# RX08.net
KiCad netlist of a schematic drawn in EAGLE
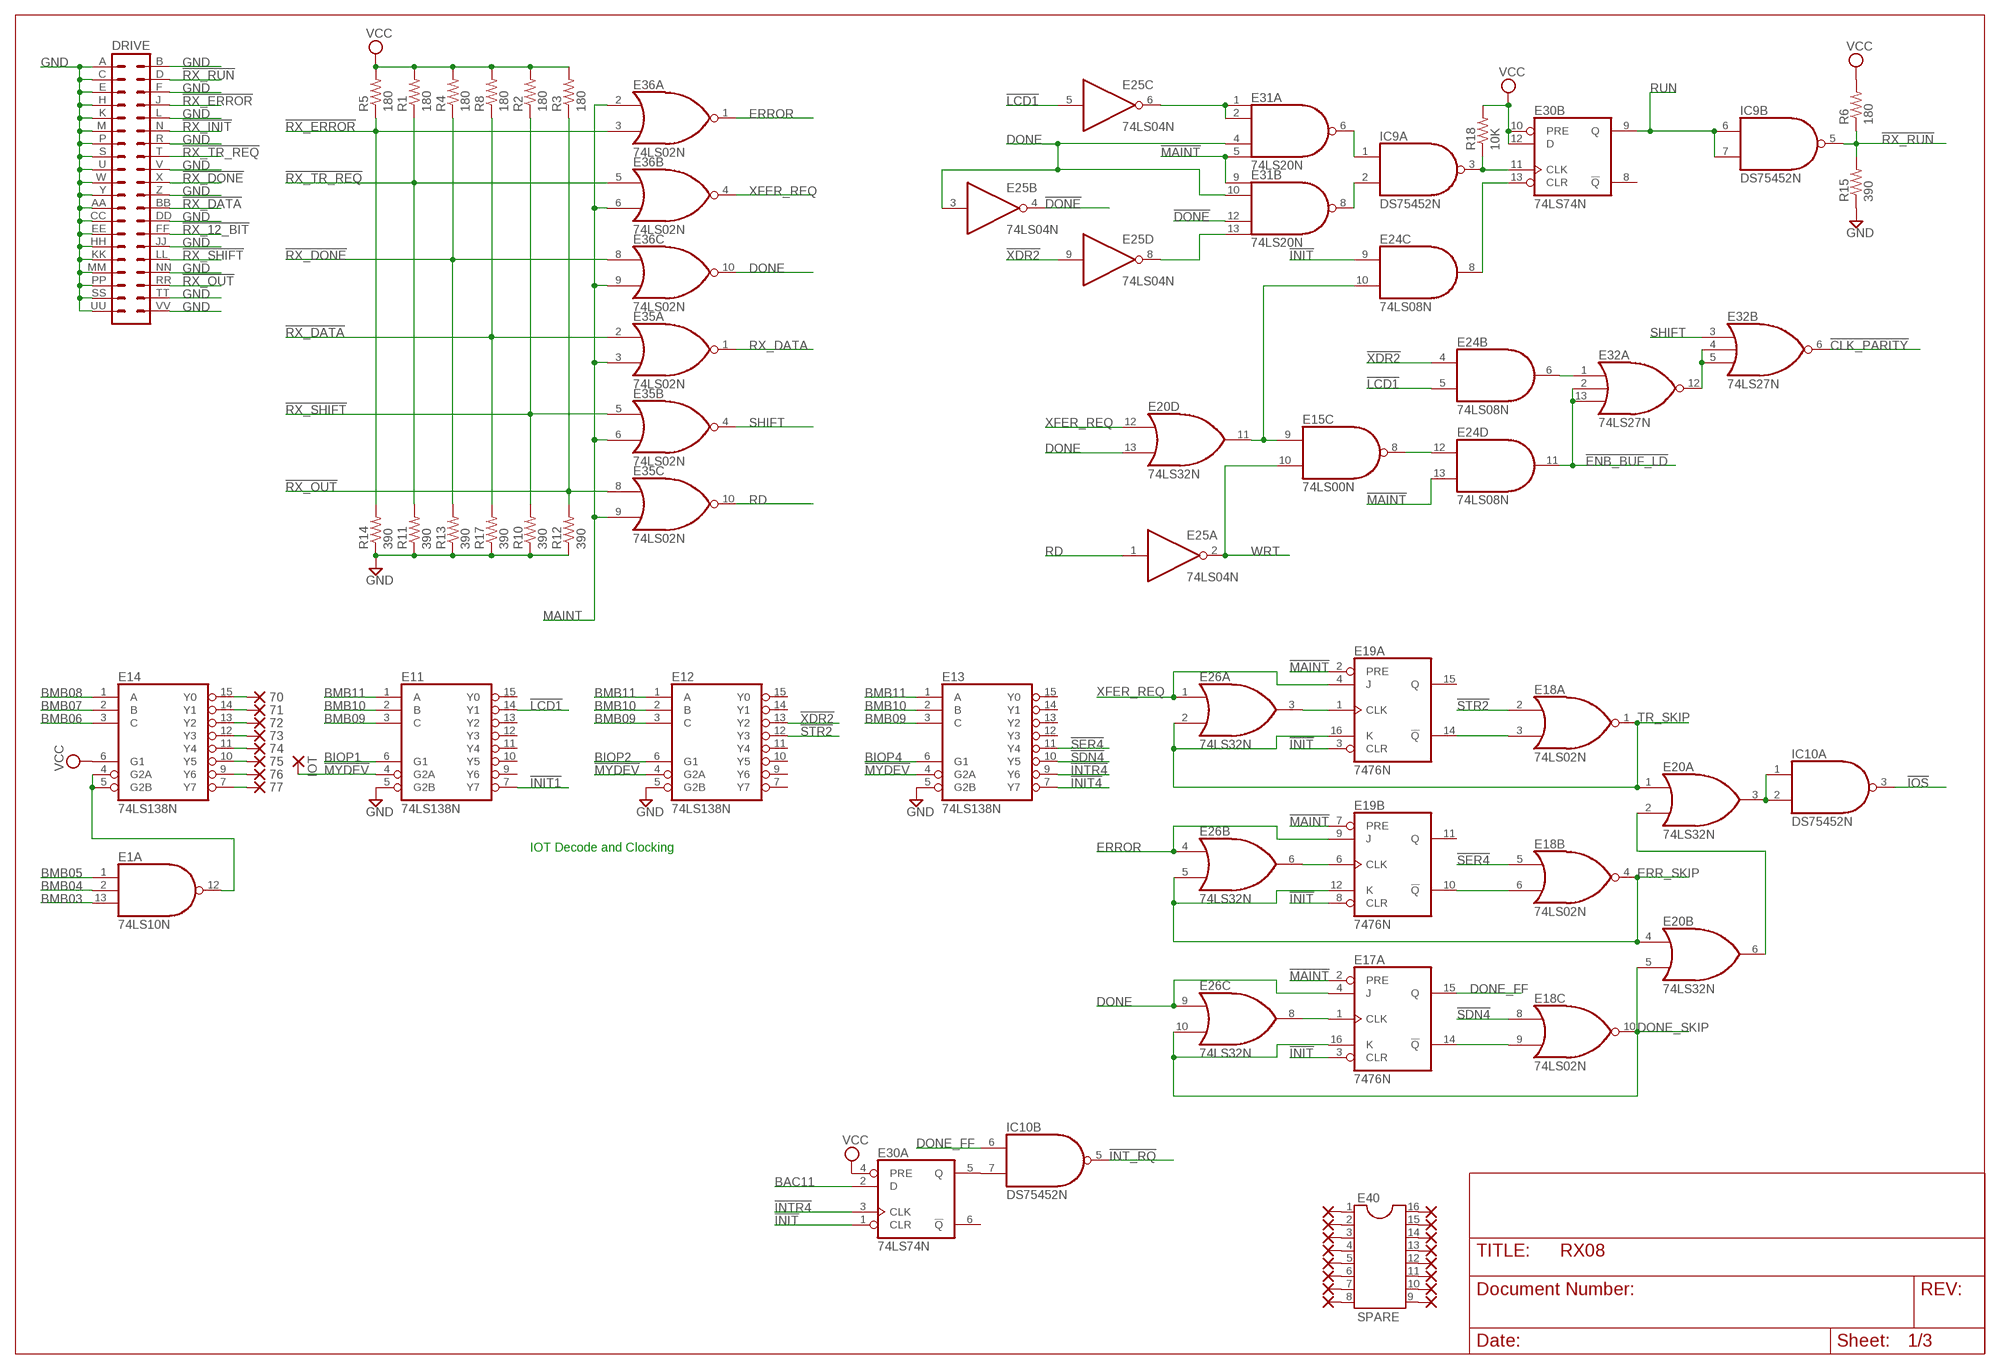
[diagram p0: schematic, sheet 1]
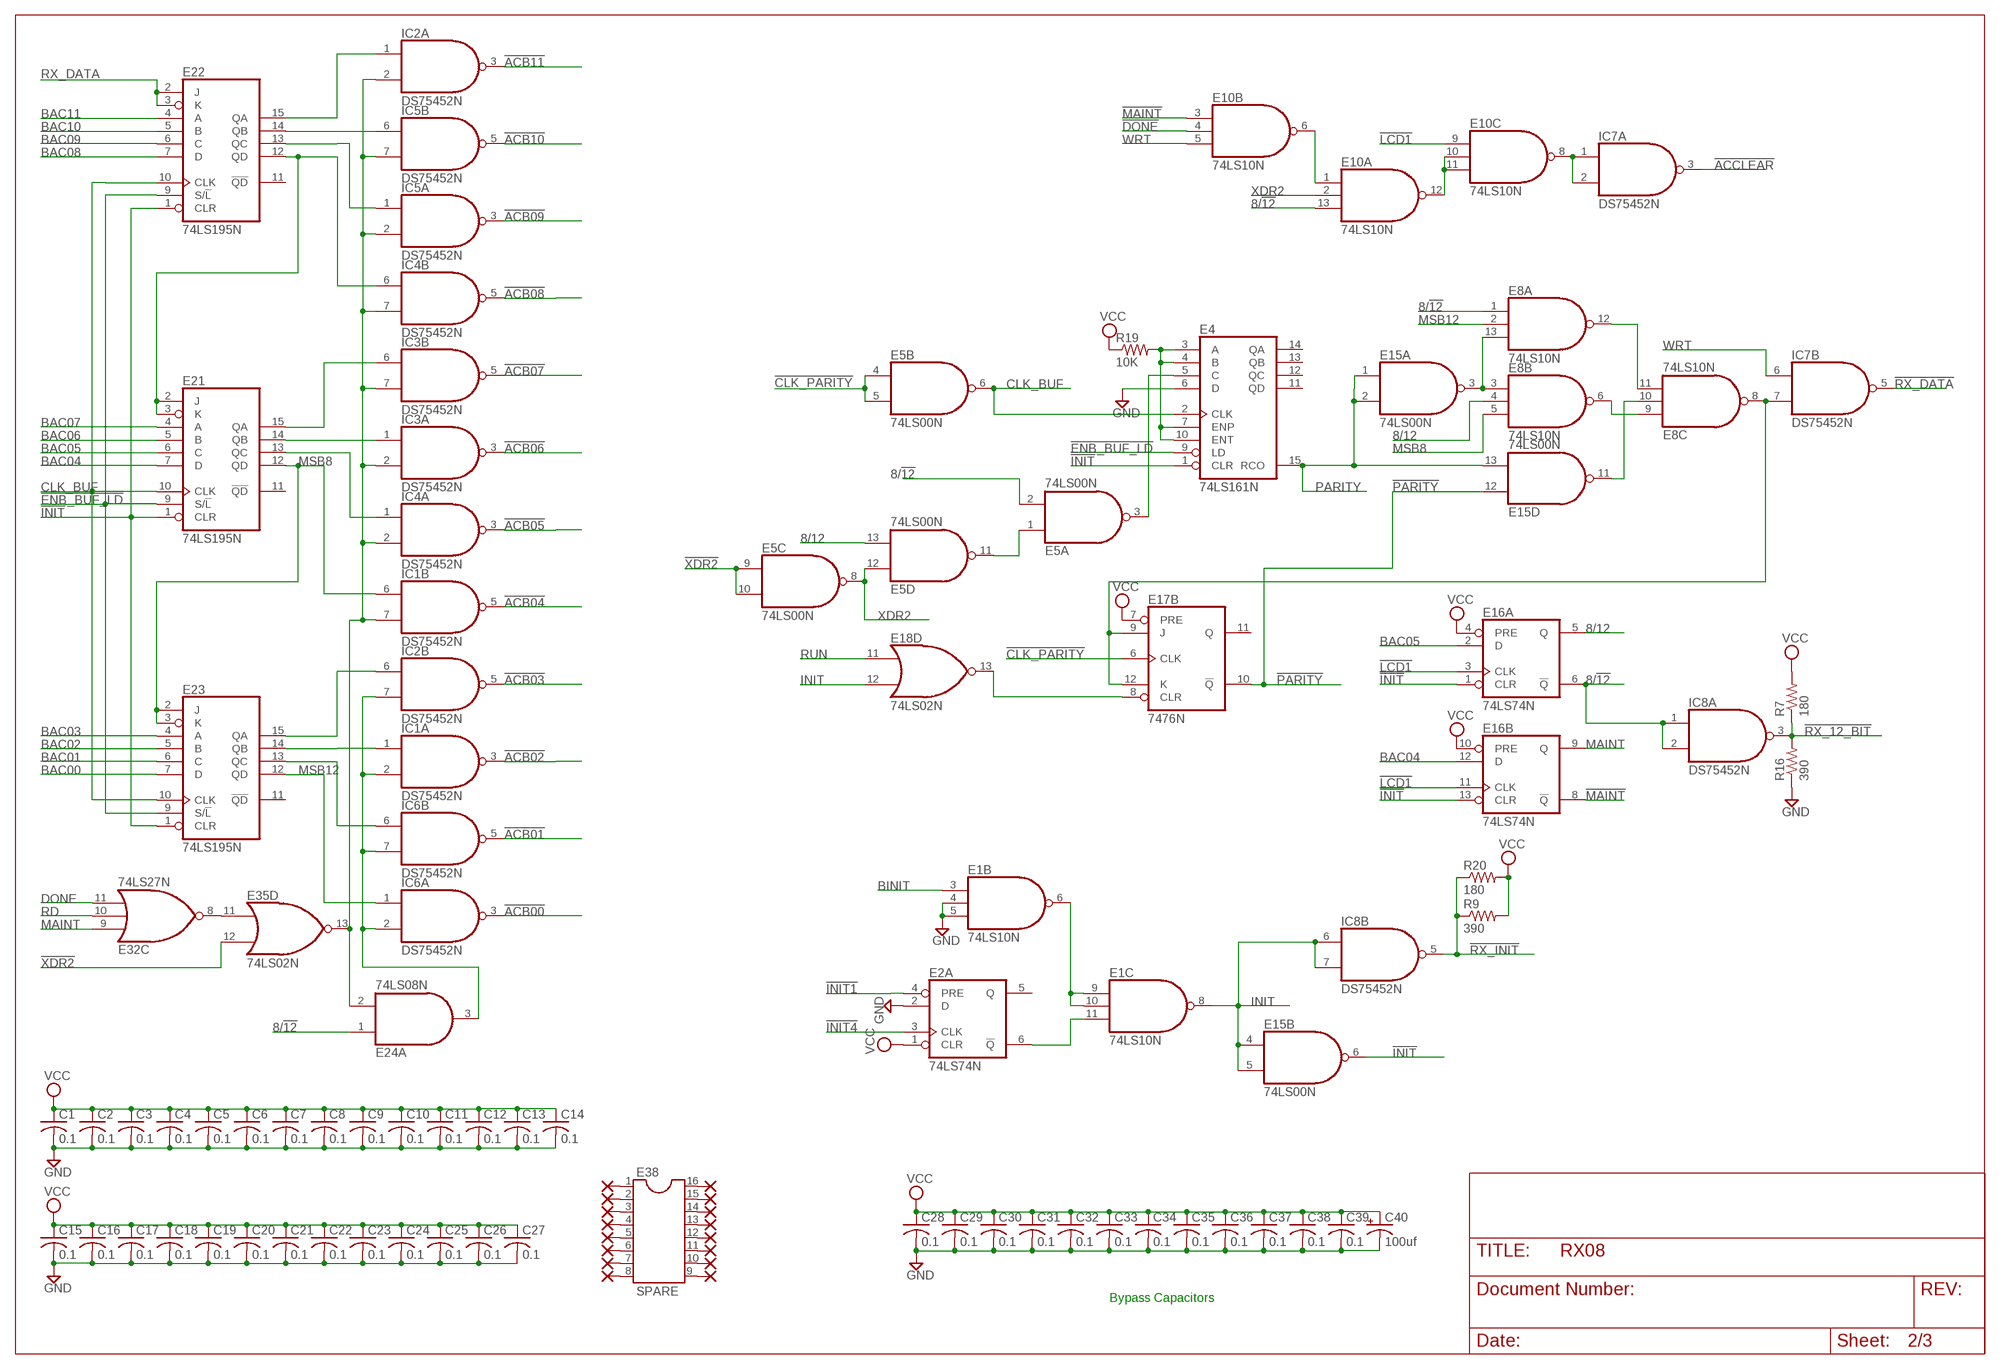
[diagram p1: schematic, sheet 2]
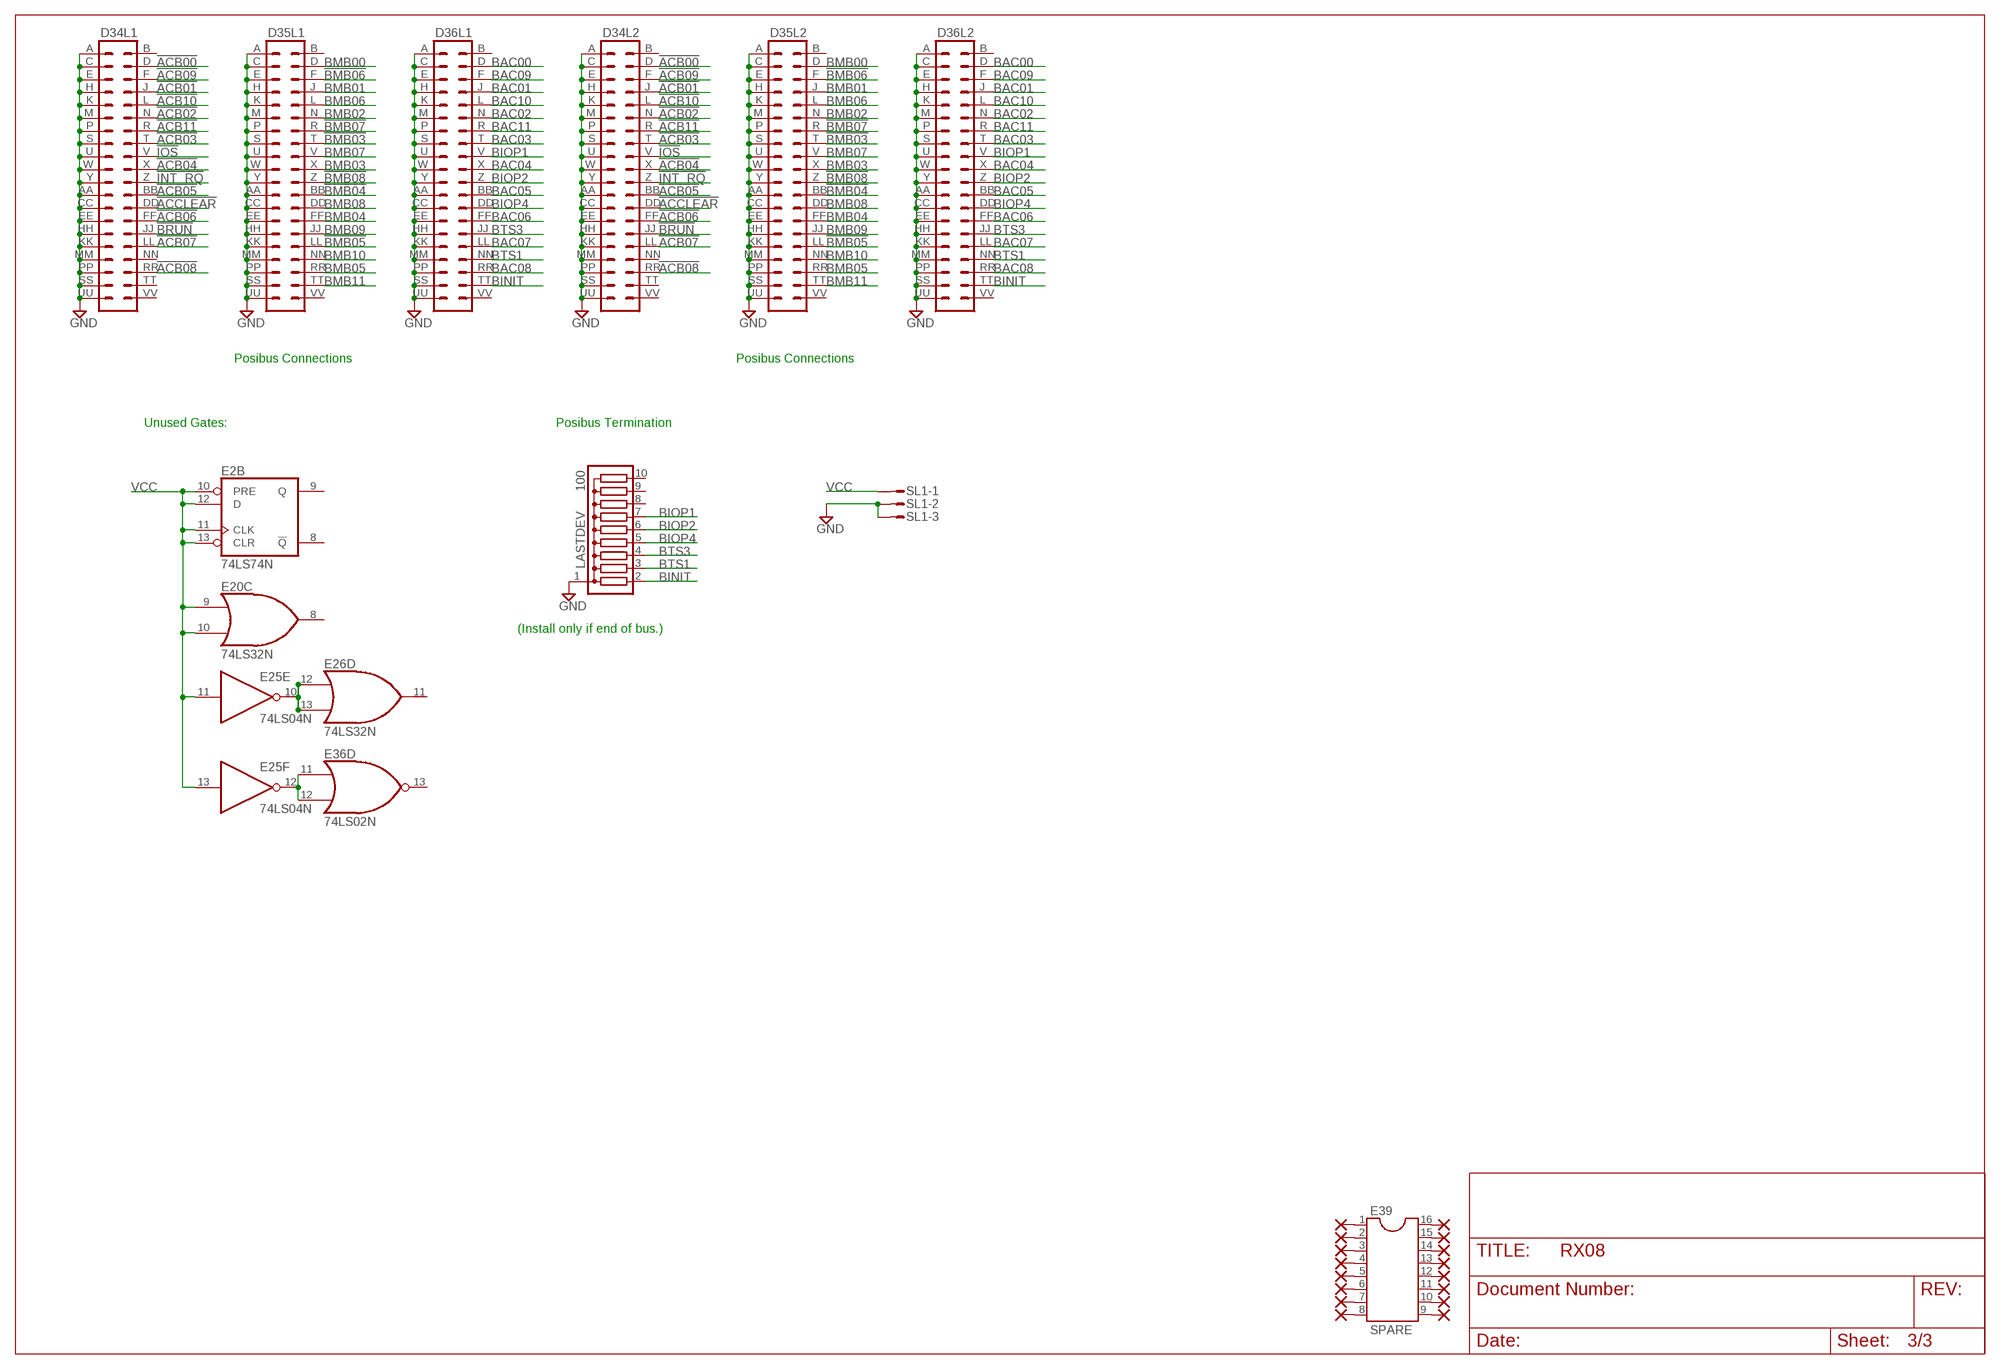
[diagram p2: schematic, sheet 3]

(export (version "E")
  (design (tool "Eeschema 10.0.6"))
  (components
    (comp (ref "C1")
      (value "0.1")
      (footprint "eagle-import:C050-025X075")
      (libsource (lib "eagle-import") (part "C-US050-025X075"))
    )
    (comp (ref "C2")
      (value "0.1")
      (footprint "eagle-import:C050-025X075")
      (libsource (lib "eagle-import") (part "C-US050-025X075"))
    )
    (comp (ref "C3")
      (value "0.1")
      (footprint "eagle-import:C050-025X075")
      (libsource (lib "eagle-import") (part "C-US050-025X075"))
    )
    (comp (ref "C4")
      (value "0.1")
      (footprint "eagle-import:C050-025X075")
      (libsource (lib "eagle-import") (part "C-US050-025X075"))
    )
    (comp (ref "C5")
      (value "0.1")
      (footprint "eagle-import:C050-025X075")
      (libsource (lib "eagle-import") (part "C-US050-025X075"))
    )
    (comp (ref "C6")
      (value "0.1")
      (footprint "eagle-import:C050-025X075")
      (libsource (lib "eagle-import") (part "C-US050-025X075"))
    )
    (comp (ref "C7")
      (value "0.1")
      (footprint "eagle-import:C050-025X075")
      (libsource (lib "eagle-import") (part "C-US050-025X075"))
    )
    (comp (ref "C8")
      (value "0.1")
      (footprint "eagle-import:C050-025X075")
      (libsource (lib "eagle-import") (part "C-US050-025X075"))
    )
    (comp (ref "C9")
      (value "0.1")
      (footprint "eagle-import:C050-025X075")
      (libsource (lib "eagle-import") (part "C-US050-025X075"))
    )
    (comp (ref "C10")
      (value "0.1")
      (footprint "eagle-import:C050-025X075")
      (libsource (lib "eagle-import") (part "C-US050-025X075"))
    )
    (comp (ref "C11")
      (value "0.1")
      (footprint "eagle-import:C050-025X075")
      (libsource (lib "eagle-import") (part "C-US050-025X075"))
    )
    (comp (ref "C12")
      (value "0.1")
      (footprint "eagle-import:C050-025X075")
      (libsource (lib "eagle-import") (part "C-US050-025X075"))
    )
    (comp (ref "C13")
      (value "0.1")
      (footprint "eagle-import:C050-025X075")
      (libsource (lib "eagle-import") (part "C-US050-025X075"))
    )
    (comp (ref "C14")
      (value "0.1")
      (footprint "eagle-import:C050-025X075")
      (libsource (lib "eagle-import") (part "C-US050-025X075"))
    )
    (comp (ref "C15")
      (value "0.1")
      (footprint "eagle-import:C050-025X075")
      (libsource (lib "eagle-import") (part "C-US050-025X075"))
    )
    (comp (ref "C16")
      (value "0.1")
      (footprint "eagle-import:C050-025X075")
      (libsource (lib "eagle-import") (part "C-US050-025X075"))
    )
    (comp (ref "C17")
      (value "0.1")
      (footprint "eagle-import:C050-025X075")
      (libsource (lib "eagle-import") (part "C-US050-025X075"))
    )
    (comp (ref "C18")
      (value "0.1")
      (footprint "eagle-import:C050-025X075")
      (libsource (lib "eagle-import") (part "C-US050-025X075"))
    )
    (comp (ref "C19")
      (value "0.1")
      (footprint "eagle-import:C050-025X075")
      (libsource (lib "eagle-import") (part "C-US050-025X075"))
    )
    (comp (ref "C20")
      (value "0.1")
      (footprint "eagle-import:C050-025X075")
      (libsource (lib "eagle-import") (part "C-US050-025X075"))
    )
    (comp (ref "C21")
      (value "0.1")
      (footprint "eagle-import:C050-025X075")
      (libsource (lib "eagle-import") (part "C-US050-025X075"))
    )
    (comp (ref "C22")
      (value "0.1")
      (footprint "eagle-import:C050-025X075")
      (libsource (lib "eagle-import") (part "C-US050-025X075"))
    )
    (comp (ref "C23")
      (value "0.1")
      (footprint "eagle-import:C050-025X075")
      (libsource (lib "eagle-import") (part "C-US050-025X075"))
    )
    (comp (ref "C24")
      (value "0.1")
      (footprint "eagle-import:C050-025X075")
      (libsource (lib "eagle-import") (part "C-US050-025X075"))
    )
    (comp (ref "C25")
      (value "0.1")
      (footprint "eagle-import:C050-025X075")
      (libsource (lib "eagle-import") (part "C-US050-025X075"))
    )
    (comp (ref "C26")
      (value "0.1")
      (footprint "eagle-import:C050-025X075")
      (libsource (lib "eagle-import") (part "C-US050-025X075"))
    )
    (comp (ref "C27")
      (value "0.1")
      (footprint "eagle-import:C050-025X075")
      (libsource (lib "eagle-import") (part "C-US050-025X075"))
    )
    (comp (ref "C28")
      (value "0.1")
      (footprint "eagle-import:C050-025X075")
      (libsource (lib "eagle-import") (part "C-US050-025X075"))
    )
    (comp (ref "C29")
      (value "0.1")
      (footprint "eagle-import:C050-025X075")
      (libsource (lib "eagle-import") (part "C-US050-025X075"))
    )
    (comp (ref "C30")
      (value "0.1")
      (footprint "eagle-import:C050-025X075")
      (libsource (lib "eagle-import") (part "C-US050-025X075"))
    )
    (comp (ref "C31")
      (value "0.1")
      (footprint "eagle-import:C050-025X075")
      (libsource (lib "eagle-import") (part "C-US050-025X075"))
    )
    (comp (ref "C32")
      (value "0.1")
      (footprint "eagle-import:C050-025X075")
      (libsource (lib "eagle-import") (part "C-US050-025X075"))
    )
    (comp (ref "C33")
      (value "0.1")
      (footprint "eagle-import:C050-025X075")
      (libsource (lib "eagle-import") (part "C-US050-025X075"))
    )
    (comp (ref "C34")
      (value "0.1")
      (footprint "eagle-import:C050-025X075")
      (libsource (lib "eagle-import") (part "C-US050-025X075"))
    )
    (comp (ref "C35")
      (value "0.1")
      (footprint "eagle-import:C050-025X075")
      (libsource (lib "eagle-import") (part "C-US050-025X075"))
    )
    (comp (ref "C36")
      (value "0.1")
      (footprint "eagle-import:C050-025X075")
      (libsource (lib "eagle-import") (part "C-US050-025X075"))
    )
    (comp (ref "C37")
      (value "0.1")
      (footprint "eagle-import:C050-025X075")
      (libsource (lib "eagle-import") (part "C-US050-025X075"))
    )
    (comp (ref "C38")
      (value "0.1")
      (footprint "eagle-import:C050-025X075")
      (libsource (lib "eagle-import") (part "C-US050-025X075"))
    )
    (comp (ref "C39")
      (value "0.1")
      (footprint "eagle-import:C050-025X075")
      (libsource (lib "eagle-import") (part "C-US050-025X075"))
    )
    (comp (ref "C40")
      (value "100uf")
      (footprint "eagle-import:E22-9")
      (libsource (lib "eagle-import") (part "CPOL-USE22-9AXIAL"))
    )
    (comp (ref "E1")
      (value "74LS10N")
      (footprint "eagle-import:DIL14")
      (libsource (lib "eagle-import") (part "7410NLS"))
    )
    (comp (ref "E2")
      (value "74LS74N")
      (footprint "eagle-import:DIL14")
      (libsource (lib "eagle-import") (part "7474NLS"))
    )
    (comp (ref "E4")
      (value "74LS161N")
      (footprint "eagle-import:DIL16")
      (libsource (lib "eagle-import") (part "74161NLS"))
    )
    (comp (ref "E5")
      (value "74LS00N")
      (footprint "eagle-import:DIL14")
      (libsource (lib "eagle-import") (part "7400NLS"))
    )
    (comp (ref "E8")
      (value "74LS10N")
      (footprint "eagle-import:DIL14")
      (libsource (lib "eagle-import") (part "7410NLS"))
    )
    (comp (ref "E10")
      (value "74LS10N")
      (footprint "eagle-import:DIL14")
      (libsource (lib "eagle-import") (part "7410NLS"))
    )
    (comp (ref "E15")
      (value "74LS00N")
      (footprint "eagle-import:DIL14")
      (libsource (lib "eagle-import") (part "7400NLS"))
    )
    (comp (ref "E16")
      (value "74LS74N")
      (footprint "eagle-import:DIL14")
      (libsource (lib "eagle-import") (part "7474NLS"))
    )
    (comp (ref "E17")
      (value "7476N")
      (footprint "eagle-import:DIL16")
      (libsource (lib "eagle-import") (part "7476N"))
    )
    (comp (ref "E18")
      (value "74LS02N")
      (footprint "eagle-import:DIL14")
      (libsource (lib "eagle-import") (part "7402NLS"))
    )
    (comp (ref "E21")
      (value "74LS195N")
      (footprint "eagle-import:DIL16")
      (libsource (lib "eagle-import") (part "74195NLS"))
    )
    (comp (ref "E22")
      (value "74LS195N")
      (footprint "eagle-import:DIL16")
      (libsource (lib "eagle-import") (part "74195NLS"))
    )
    (comp (ref "E23")
      (value "74LS195N")
      (footprint "eagle-import:DIL16")
      (libsource (lib "eagle-import") (part "74195NLS"))
    )
    (comp (ref "E24")
      (value "74LS08N")
      (footprint "eagle-import:DIL14")
      (libsource (lib "eagle-import") (part "7408NLS"))
    )
    (comp (ref "E32")
      (value "74LS27N")
      (footprint "eagle-import:DIL14")
      (libsource (lib "eagle-import") (part "7427NLS"))
    )
    (comp (ref "E35")
      (value "74LS02N")
      (footprint "eagle-import:DIL14")
      (libsource (lib "eagle-import") (part "7402NLS"))
    )
    (comp (ref "E38")
      (value "SPARE")
      (footprint "eagle-import:DIL16")
      (libsource (lib "eagle-import") (part "DIL16"))
    )
    (comp (ref "IC1")
      (value "DS75452N")
      (footprint "eagle-import:DIL08")
      (libsource (lib "eagle-import") (part "DS75452N"))
    )
    (comp (ref "IC2")
      (value "DS75452N")
      (footprint "eagle-import:DIL08")
      (libsource (lib "eagle-import") (part "DS75452N"))
    )
    (comp (ref "IC3")
      (value "DS75452N")
      (footprint "eagle-import:DIL08")
      (libsource (lib "eagle-import") (part "DS75452N"))
    )
    (comp (ref "IC4")
      (value "DS75452N")
      (footprint "eagle-import:DIL08")
      (libsource (lib "eagle-import") (part "DS75452N"))
    )
    (comp (ref "IC5")
      (value "DS75452N")
      (footprint "eagle-import:DIL08")
      (libsource (lib "eagle-import") (part "DS75452N"))
    )
    (comp (ref "IC6")
      (value "DS75452N")
      (footprint "eagle-import:DIL08")
      (libsource (lib "eagle-import") (part "DS75452N"))
    )
    (comp (ref "IC7")
      (value "DS75452N")
      (footprint "eagle-import:DIL08")
      (libsource (lib "eagle-import") (part "DS75452N"))
    )
    (comp (ref "IC8")
      (value "DS75452N")
      (footprint "eagle-import:DIL08")
      (libsource (lib "eagle-import") (part "DS75452N"))
    )
    (comp (ref "PAD10")
      (value "1,6/0,8")
      (footprint "eagle-import:1,6_0,8")
      (libsource (lib "eagle-import") (part "1,6/0,8"))
    )
    (comp (ref "PAD11")
      (value "1,6/0,8")
      (footprint "eagle-import:1,6_0,8")
      (libsource (lib "eagle-import") (part "1,6/0,8"))
    )
    (comp (ref "PAD12")
      (value "1,6/0,8")
      (footprint "eagle-import:1,6_0,8")
      (libsource (lib "eagle-import") (part "1,6/0,8"))
    )
    (comp (ref "PAD13")
      (value "1,6/0,8")
      (footprint "eagle-import:1,6_0,8")
      (libsource (lib "eagle-import") (part "1,6/0,8"))
    )
    (comp (ref "PAD14")
      (value "1,6/0,8")
      (footprint "eagle-import:1,6_0,8")
      (libsource (lib "eagle-import") (part "1,6/0,8"))
    )
    (comp (ref "PAD15")
      (value "1,6/0,8")
      (footprint "eagle-import:1,6_0,8")
      (libsource (lib "eagle-import") (part "1,6/0,8"))
    )
    (comp (ref "PAD16")
      (value "1,6/0,8")
      (footprint "eagle-import:1,6_0,8")
      (libsource (lib "eagle-import") (part "1,6/0,8"))
    )
    (comp (ref "PAD17")
      (value "1,6/0,8")
      (footprint "eagle-import:1,6_0,8")
      (libsource (lib "eagle-import") (part "1,6/0,8"))
    )
    (comp (ref "PAD20")
      (value "1,6/0,8")
      (footprint "eagle-import:1,6_0,8")
      (libsource (lib "eagle-import") (part "1,6/0,8"))
    )
    (comp (ref "PAD21")
      (value "1,6/0,8")
      (footprint "eagle-import:1,6_0,8")
      (libsource (lib "eagle-import") (part "1,6/0,8"))
    )
    (comp (ref "PAD22")
      (value "1,6/0,8")
      (footprint "eagle-import:1,6_0,8")
      (libsource (lib "eagle-import") (part "1,6/0,8"))
    )
    (comp (ref "PAD23")
      (value "1,6/0,8")
      (footprint "eagle-import:1,6_0,8")
      (libsource (lib "eagle-import") (part "1,6/0,8"))
    )
    (comp (ref "PAD24")
      (value "1,6/0,8")
      (footprint "eagle-import:1,6_0,8")
      (libsource (lib "eagle-import") (part "1,6/0,8"))
    )
    (comp (ref "PAD25")
      (value "1,6/0,8")
      (footprint "eagle-import:1,6_0,8")
      (libsource (lib "eagle-import") (part "1,6/0,8"))
    )
    (comp (ref "PAD26")
      (value "1,6/0,8")
      (footprint "eagle-import:1,6_0,8")
      (libsource (lib "eagle-import") (part "1,6/0,8"))
    )
    (comp (ref "PAD27")
      (value "1,6/0,8")
      (footprint "eagle-import:1,6_0,8")
      (libsource (lib "eagle-import") (part "1,6/0,8"))
    )
    (comp (ref "R7")
      (value "180")
      (footprint "eagle-import:0207_10")
      (libsource (lib "eagle-import") (part "R-US_0207/10"))
    )
    (comp (ref "R9")
      (value "390")
      (footprint "eagle-import:0207_10")
      (libsource (lib "eagle-import") (part "R-US_0207/10"))
    )
    (comp (ref "R16")
      (value "390")
      (footprint "eagle-import:0207_10")
      (libsource (lib "eagle-import") (part "R-US_0207/10"))
    )
    (comp (ref "R19")
      (value "10K")
      (footprint "eagle-import:0207_10")
      (libsource (lib "eagle-import") (part "R-US_0207/10"))
    )
    (comp (ref "R20")
      (value "180")
      (footprint "eagle-import:0207_10")
      (libsource (lib "eagle-import") (part "R-US_0207/10"))
    )
    (comp (ref "D34L1")
      (value "DEC40PINV")
      (footprint "eagle-import:DEC40PINV")
      (libsource (lib "eagle-import") (part "DEC40PINV"))
    )
    (comp (ref "D34L2")
      (value "DEC40PINV")
      (footprint "eagle-import:DEC40PINV")
      (libsource (lib "eagle-import") (part "DEC40PINV"))
    )
    (comp (ref "D35L1")
      (value "DEC40PINV")
      (footprint "eagle-import:DEC40PINV")
      (libsource (lib "eagle-import") (part "DEC40PINV"))
    )
    (comp (ref "D35L2")
      (value "DEC40PINV")
      (footprint "eagle-import:DEC40PINV")
      (libsource (lib "eagle-import") (part "DEC40PINV"))
    )
    (comp (ref "D36L1")
      (value "DEC40PINV")
      (footprint "eagle-import:DEC40PINV")
      (libsource (lib "eagle-import") (part "DEC40PINV"))
    )
    (comp (ref "D36L2")
      (value "DEC40PINV")
      (footprint "eagle-import:DEC40PINV")
      (libsource (lib "eagle-import") (part "DEC40PINV"))
    )
    (comp (ref "E20")
      (value "74LS32N")
      (footprint "eagle-import:DIL14")
      (libsource (lib "eagle-import") (part "7432NLS"))
    )
    (comp (ref "E25")
      (value "74LS04N")
      (footprint "eagle-import:DIL14")
      (libsource (lib "eagle-import") (part "7404NLS"))
    )
    (comp (ref "E26")
      (value "74LS32N")
      (footprint "eagle-import:DIL14")
      (libsource (lib "eagle-import") (part "7432NLS"))
    )
    (comp (ref "E36")
      (value "74LS02N")
      (footprint "eagle-import:DIL14")
      (libsource (lib "eagle-import") (part "7402NLS"))
    )
    (comp (ref "E39")
      (value "SPARE")
      (footprint "eagle-import:DIL16")
      (libsource (lib "eagle-import") (part "DIL16"))
    )
    (comp (ref "LASTDEV")
      (value "100")
      (footprint "eagle-import:SIL10")
      (libsource (lib "eagle-import") (part "G09R"))
    )
    (comp (ref "PAD42")
      (value "1,6/0,8")
      (footprint "eagle-import:1,6_0,8")
      (libsource (lib "eagle-import") (part "1,6/0,8"))
    )
    (comp (ref "PAD43")
      (value "1,6/0,8")
      (footprint "eagle-import:1,6_0,8")
      (libsource (lib "eagle-import") (part "1,6/0,8"))
    )
    (comp (ref "PAD44")
      (value "1,6/0,8")
      (footprint "eagle-import:1,6_0,8")
      (libsource (lib "eagle-import") (part "1,6/0,8"))
    )
    (comp (ref "PAD45")
      (value "1,6/0,8")
      (footprint "eagle-import:1,6_0,8")
      (libsource (lib "eagle-import") (part "1,6/0,8"))
    )
    (comp (ref "PAD46")
      (value "1,6/0,8")
      (footprint "eagle-import:1,6_0,8")
      (libsource (lib "eagle-import") (part "1,6/0,8"))
    )
    (comp (ref "PAD47")
      (value "1,6/0,8")
      (footprint "eagle-import:1,6_0,8")
      (libsource (lib "eagle-import") (part "1,6/0,8"))
    )
    (comp (ref "PAD48")
      (value "1,6/0,8")
      (footprint "eagle-import:1,6_0,8")
      (libsource (lib "eagle-import") (part "1,6/0,8"))
    )
    (comp (ref "PAD49")
      (value "1,6/0,8")
      (footprint "eagle-import:1,6_0,8")
      (libsource (lib "eagle-import") (part "1,6/0,8"))
    )
    (comp (ref "PAD50")
      (value "1,6/0,8")
      (footprint "eagle-import:1,6_0,8")
      (libsource (lib "eagle-import") (part "1,6/0,8"))
    )
    (comp (ref "PAD51")
      (value "1,6/0,8")
      (footprint "eagle-import:1,6_0,8")
      (libsource (lib "eagle-import") (part "1,6/0,8"))
    )
    (comp (ref "PAD52")
      (value "1,6/0,8")
      (footprint "eagle-import:1,6_0,8")
      (libsource (lib "eagle-import") (part "1,6/0,8"))
    )
    (comp (ref "PAD53")
      (value "1,6/0,8")
      (footprint "eagle-import:1,6_0,8")
      (libsource (lib "eagle-import") (part "1,6/0,8"))
    )
    (comp (ref "PAD54")
      (value "1,6/0,8")
      (footprint "eagle-import:1,6_0,8")
      (libsource (lib "eagle-import") (part "1,6/0,8"))
    )
    (comp (ref "PAD55")
      (value "1,6/0,8")
      (footprint "eagle-import:1,6_0,8")
      (libsource (lib "eagle-import") (part "1,6/0,8"))
    )
    (comp (ref "PAD56")
      (value "1,6/0,8")
      (footprint "eagle-import:1,6_0,8")
      (libsource (lib "eagle-import") (part "1,6/0,8"))
    )
    (comp (ref "PAD57")
      (value "1,6/0,8")
      (footprint "eagle-import:1,6_0,8")
      (libsource (lib "eagle-import") (part "1,6/0,8"))
    )
    (comp (ref "SL1")
      (value "MA04S")
      (footprint "eagle-import:04PA")
      (libsource (lib "eagle-import") (part "MA04S"))
    )
    (comp (ref "70")
      (value "1,6/0,8")
      (footprint "eagle-import:1,6_0,8")
      (libsource (lib "eagle-import") (part "1,6/0,8"))
    )
    (comp (ref "71")
      (value "1,6/0,8")
      (footprint "eagle-import:1,6_0,8")
      (libsource (lib "eagle-import") (part "1,6/0,8"))
    )
    (comp (ref "72")
      (value "1,6/0,8")
      (footprint "eagle-import:1,6_0,8")
      (libsource (lib "eagle-import") (part "1,6/0,8"))
    )
    (comp (ref "73")
      (value "1,6/0,8")
      (footprint "eagle-import:1,6_0,8")
      (libsource (lib "eagle-import") (part "1,6/0,8"))
    )
    (comp (ref "74")
      (value "1,6/0,8")
      (footprint "eagle-import:1,6_0,8")
      (libsource (lib "eagle-import") (part "1,6/0,8"))
    )
    (comp (ref "75")
      (value "1,6/0,8")
      (footprint "eagle-import:1,6_0,8")
      (libsource (lib "eagle-import") (part "1,6/0,8"))
    )
    (comp (ref "76")
      (value "1,6/0,8")
      (footprint "eagle-import:1,6_0,8")
      (libsource (lib "eagle-import") (part "1,6/0,8"))
    )
    (comp (ref "77")
      (value "1,6/0,8")
      (footprint "eagle-import:1,6_0,8")
      (libsource (lib "eagle-import") (part "1,6/0,8"))
    )
    (comp (ref "DRIVE")
      (value "DEC40PINV")
      (footprint "eagle-import:DEC40PINV")
      (libsource (lib "eagle-import") (part "DEC40PINV"))
    )
    (comp (ref "E11")
      (value "74LS138N")
      (footprint "eagle-import:DIL16")
      (libsource (lib "eagle-import") (part "74138NLS"))
    )
    (comp (ref "E12")
      (value "74LS138N")
      (footprint "eagle-import:DIL16")
      (libsource (lib "eagle-import") (part "74138NLS"))
    )
    (comp (ref "E13")
      (value "74LS138N")
      (footprint "eagle-import:DIL16")
      (libsource (lib "eagle-import") (part "74138NLS"))
    )
    (comp (ref "E14")
      (value "74LS138N")
      (footprint "eagle-import:DIL16")
      (libsource (lib "eagle-import") (part "74138NLS"))
    )
    (comp (ref "E19")
      (value "7476N")
      (footprint "eagle-import:DIL16")
      (libsource (lib "eagle-import") (part "7476N"))
    )
    (comp (ref "E30")
      (value "74LS74N")
      (footprint "eagle-import:DIL14")
      (libsource (lib "eagle-import") (part "7474NLS"))
    )
    (comp (ref "E31")
      (value "74LS20N")
      (footprint "eagle-import:DIL14")
      (libsource (lib "eagle-import") (part "7420NLS"))
    )
    (comp (ref "E40")
      (value "SPARE")
      (footprint "eagle-import:DIL16")
      (libsource (lib "eagle-import") (part "DIL16"))
    )
    (comp (ref "IC9")
      (value "DS75452N")
      (footprint "eagle-import:DIL08")
      (libsource (lib "eagle-import") (part "DS75452N"))
    )
    (comp (ref "IC10")
      (value "DS75452N")
      (footprint "eagle-import:DIL08")
      (libsource (lib "eagle-import") (part "DS75452N"))
    )
    (comp (ref "IOT")
      (value "1,6/0,8")
      (footprint "eagle-import:1,6_0,8")
      (libsource (lib "eagle-import") (part "1,6/0,8"))
    )
    (comp (ref "PAD18")
      (value "1,6/0,8")
      (footprint "eagle-import:1,6_0,8")
      (libsource (lib "eagle-import") (part "1,6/0,8"))
    )
    (comp (ref "PAD19")
      (value "1,6/0,8")
      (footprint "eagle-import:1,6_0,8")
      (libsource (lib "eagle-import") (part "1,6/0,8"))
    )
    (comp (ref "PAD28")
      (value "1,6/0,8")
      (footprint "eagle-import:1,6_0,8")
      (libsource (lib "eagle-import") (part "1,6/0,8"))
    )
    (comp (ref "PAD29")
      (value "1,6/0,8")
      (footprint "eagle-import:1,6_0,8")
      (libsource (lib "eagle-import") (part "1,6/0,8"))
    )
    (comp (ref "PAD30")
      (value "1,6/0,8")
      (footprint "eagle-import:1,6_0,8")
      (libsource (lib "eagle-import") (part "1,6/0,8"))
    )
    (comp (ref "PAD31")
      (value "1,6/0,8")
      (footprint "eagle-import:1,6_0,8")
      (libsource (lib "eagle-import") (part "1,6/0,8"))
    )
    (comp (ref "PAD32")
      (value "1,6/0,8")
      (footprint "eagle-import:1,6_0,8")
      (libsource (lib "eagle-import") (part "1,6/0,8"))
    )
    (comp (ref "PAD33")
      (value "1,6/0,8")
      (footprint "eagle-import:1,6_0,8")
      (libsource (lib "eagle-import") (part "1,6/0,8"))
    )
    (comp (ref "PAD34")
      (value "1,6/0,8")
      (footprint "eagle-import:1,6_0,8")
      (libsource (lib "eagle-import") (part "1,6/0,8"))
    )
    (comp (ref "PAD35")
      (value "1,6/0,8")
      (footprint "eagle-import:1,6_0,8")
      (libsource (lib "eagle-import") (part "1,6/0,8"))
    )
    (comp (ref "PAD36")
      (value "1,6/0,8")
      (footprint "eagle-import:1,6_0,8")
      (libsource (lib "eagle-import") (part "1,6/0,8"))
    )
    (comp (ref "PAD37")
      (value "1,6/0,8")
      (footprint "eagle-import:1,6_0,8")
      (libsource (lib "eagle-import") (part "1,6/0,8"))
    )
    (comp (ref "PAD38")
      (value "1,6/0,8")
      (footprint "eagle-import:1,6_0,8")
      (libsource (lib "eagle-import") (part "1,6/0,8"))
    )
    (comp (ref "PAD39")
      (value "1,6/0,8")
      (footprint "eagle-import:1,6_0,8")
      (libsource (lib "eagle-import") (part "1,6/0,8"))
    )
    (comp (ref "PAD40")
      (value "1,6/0,8")
      (footprint "eagle-import:1,6_0,8")
      (libsource (lib "eagle-import") (part "1,6/0,8"))
    )
    (comp (ref "PAD41")
      (value "1,6/0,8")
      (footprint "eagle-import:1,6_0,8")
      (libsource (lib "eagle-import") (part "1,6/0,8"))
    )
    (comp (ref "R1")
      (value "180")
      (footprint "eagle-import:0207_10")
      (libsource (lib "eagle-import") (part "R-US_0207/10"))
    )
    (comp (ref "R2")
      (value "180")
      (footprint "eagle-import:0207_10")
      (libsource (lib "eagle-import") (part "R-US_0207/10"))
    )
    (comp (ref "R3")
      (value "180")
      (footprint "eagle-import:0207_10")
      (libsource (lib "eagle-import") (part "R-US_0207/10"))
    )
    (comp (ref "R4")
      (value "180")
      (footprint "eagle-import:0207_10")
      (libsource (lib "eagle-import") (part "R-US_0207/10"))
    )
    (comp (ref "R5")
      (value "180")
      (footprint "eagle-import:0207_10")
      (libsource (lib "eagle-import") (part "R-US_0207/10"))
    )
    (comp (ref "R6")
      (value "180")
      (footprint "eagle-import:0207_10")
      (libsource (lib "eagle-import") (part "R-US_0207/10"))
    )
    (comp (ref "R8")
      (value "180")
      (footprint "eagle-import:0207_10")
      (libsource (lib "eagle-import") (part "R-US_0207/10"))
    )
    (comp (ref "R10")
      (value "390")
      (footprint "eagle-import:0207_10")
      (libsource (lib "eagle-import") (part "R-US_0207/10"))
    )
    (comp (ref "R11")
      (value "390")
      (footprint "eagle-import:0207_10")
      (libsource (lib "eagle-import") (part "R-US_0207/10"))
    )
    (comp (ref "R12")
      (value "390")
      (footprint "eagle-import:0207_10")
      (libsource (lib "eagle-import") (part "R-US_0207/10"))
    )
    (comp (ref "R13")
      (value "390")
      (footprint "eagle-import:0207_10")
      (libsource (lib "eagle-import") (part "R-US_0207/10"))
    )
    (comp (ref "R14")
      (value "390")
      (footprint "eagle-import:0207_10")
      (libsource (lib "eagle-import") (part "R-US_0207/10"))
    )
    (comp (ref "R15")
      (value "390")
      (footprint "eagle-import:0207_10")
      (libsource (lib "eagle-import") (part "R-US_0207/10"))
    )
    (comp (ref "R17")
      (value "390")
      (footprint "eagle-import:0207_10")
      (libsource (lib "eagle-import") (part "R-US_0207/10"))
    )
    (comp (ref "R18")
      (value "10K")
      (footprint "eagle-import:0207_10")
      (libsource (lib "eagle-import") (part "R-US_0207/10"))
    )
  )
  (nets
    (net (code "1") (name "8{slash}12") (class "Default")
      (node (ref "E16") (pin "5") (pinfunction "Q_5") (pintype "output"))
      (node (ref "E5") (pin "13") (pinfunction "I1_13") (pintype "input"))
      (node (ref "E8") (pin "4") (pinfunction "I1_4") (pintype "input"))
    )
    (net (code "2") (name "8{slash}~{12}") (class "Default")
      (node (ref "E10") (pin "13") (pinfunction "I2_13") (pintype "input"))
      (node (ref "E16") (pin "6") (pinfunction "~{Q}_6") (pintype "output"))
      (node (ref "E24") (pin "1") (pinfunction "I0_1") (pintype "input"))
      (node (ref "E5") (pin "2") (pinfunction "I1_2") (pintype "input"))
      (node (ref "E8") (pin "1") (pinfunction "I0_1") (pintype "input"))
      (node (ref "IC8") (pin "1") (pinfunction "I0_1") (pintype "input"))
      (node (ref "IC8") (pin "2") (pinfunction "I1_2") (pintype "input"))
    )
    (net (code "3") (name "BAC00") (class "Default")
      (node (ref "D36L1") (pin "D") (pinfunction "4_D") (pintype "bidirectional"))
      (node (ref "D36L2") (pin "D") (pinfunction "4_D") (pintype "bidirectional"))
      (node (ref "E23") (pin "7") (pinfunction "D_7") (pintype "input"))
    )
    (net (code "4") (name "BAC01") (class "Default")
      (node (ref "D36L1") (pin "J") (pinfunction "8_J") (pintype "bidirectional"))
      (node (ref "D36L2") (pin "J") (pinfunction "8_J") (pintype "bidirectional"))
      (node (ref "E23") (pin "6") (pinfunction "C_6") (pintype "input"))
    )
    (net (code "5") (name "BAC02") (class "Default")
      (node (ref "D36L1") (pin "N") (pinfunction "12_N") (pintype "bidirectional"))
      (node (ref "D36L2") (pin "N") (pinfunction "12_N") (pintype "bidirectional"))
      (node (ref "E23") (pin "5") (pinfunction "B_5") (pintype "input"))
    )
    (net (code "6") (name "BAC03") (class "Default")
      (node (ref "D36L1") (pin "T") (pinfunction "16_T") (pintype "bidirectional"))
      (node (ref "D36L2") (pin "T") (pinfunction "16_T") (pintype "bidirectional"))
      (node (ref "E23") (pin "4") (pinfunction "A_4") (pintype "input"))
    )
    (net (code "7") (name "BAC04") (class "Default")
      (node (ref "D36L1") (pin "X") (pinfunction "20_X") (pintype "bidirectional"))
      (node (ref "D36L2") (pin "X") (pinfunction "20_X") (pintype "bidirectional"))
      (node (ref "E16") (pin "12") (pinfunction "D_12") (pintype "input"))
      (node (ref "E21") (pin "7") (pinfunction "D_7") (pintype "input"))
    )
    (net (code "8") (name "BAC05") (class "Default")
      (node (ref "D36L1") (pin "BB") (pinfunction "24_BB") (pintype "bidirectional"))
      (node (ref "D36L2") (pin "BB") (pinfunction "24_BB") (pintype "bidirectional"))
      (node (ref "E16") (pin "2") (pinfunction "D_2") (pintype "input"))
      (node (ref "E21") (pin "6") (pinfunction "C_6") (pintype "input"))
    )
    (net (code "9") (name "BAC06") (class "Default")
      (node (ref "D36L1") (pin "FF") (pinfunction "28_FF") (pintype "bidirectional"))
      (node (ref "D36L2") (pin "FF") (pinfunction "28_FF") (pintype "bidirectional"))
      (node (ref "E21") (pin "5") (pinfunction "B_5") (pintype "input"))
    )
    (net (code "10") (name "BAC07") (class "Default")
      (node (ref "D36L1") (pin "LL") (pinfunction "32_LL") (pintype "bidirectional"))
      (node (ref "D36L2") (pin "LL") (pinfunction "32_LL") (pintype "bidirectional"))
      (node (ref "E21") (pin "4") (pinfunction "A_4") (pintype "input"))
    )
    (net (code "11") (name "BAC08") (class "Default")
      (node (ref "D36L1") (pin "RR") (pinfunction "36_RR") (pintype "bidirectional"))
      (node (ref "D36L2") (pin "RR") (pinfunction "36_RR") (pintype "bidirectional"))
      (node (ref "E22") (pin "7") (pinfunction "D_7") (pintype "input"))
    )
    (net (code "12") (name "BAC09") (class "Default")
      (node (ref "D36L1") (pin "F") (pinfunction "6_F") (pintype "bidirectional"))
      (node (ref "D36L2") (pin "F") (pinfunction "6_F") (pintype "bidirectional"))
      (node (ref "E22") (pin "6") (pinfunction "C_6") (pintype "input"))
    )
    (net (code "13") (name "BAC10") (class "Default")
      (node (ref "D36L1") (pin "L") (pinfunction "10_L") (pintype "bidirectional"))
      (node (ref "D36L2") (pin "L") (pinfunction "10_L") (pintype "bidirectional"))
      (node (ref "E22") (pin "5") (pinfunction "B_5") (pintype "input"))
    )
    (net (code "14") (name "BAC11") (class "Default")
      (node (ref "D36L1") (pin "R") (pinfunction "14_R") (pintype "bidirectional"))
      (node (ref "D36L2") (pin "R") (pinfunction "14_R") (pintype "bidirectional"))
      (node (ref "E22") (pin "4") (pinfunction "A_4") (pintype "input"))
      (node (ref "E30") (pin "2") (pinfunction "D_2") (pintype "input"))
    )
    (net (code "15") (name "BINIT") (class "Default")
      (node (ref "D36L1") (pin "TT") (pinfunction "38_TT") (pintype "bidirectional"))
      (node (ref "D36L2") (pin "TT") (pinfunction "38_TT") (pintype "bidirectional"))
      (node (ref "E1") (pin "3") (pinfunction "I0_3") (pintype "input"))
      (node (ref "LASTDEV") (pin "2") (pinfunction "2_2") (pintype "passive"))
    )
    (net (code "16") (name "BIOP1") (class "Default")
      (node (ref "D36L1") (pin "V") (pinfunction "18_V") (pintype "bidirectional"))
      (node (ref "D36L2") (pin "V") (pinfunction "18_V") (pintype "bidirectional"))
      (node (ref "E11") (pin "6") (pinfunction "G1_6") (pintype "input"))
      (node (ref "LASTDEV") (pin "7") (pinfunction "7_7") (pintype "passive"))
    )
    (net (code "17") (name "BIOP2") (class "Default")
      (node (ref "D36L1") (pin "Z") (pinfunction "22_Z") (pintype "bidirectional"))
      (node (ref "D36L2") (pin "Z") (pinfunction "22_Z") (pintype "bidirectional"))
      (node (ref "E12") (pin "6") (pinfunction "G1_6") (pintype "input"))
      (node (ref "LASTDEV") (pin "6") (pinfunction "6_6") (pintype "passive"))
    )
    (net (code "18") (name "BIOP4") (class "Default")
      (node (ref "D36L1") (pin "DD") (pinfunction "26_DD") (pintype "bidirectional"))
      (node (ref "D36L2") (pin "DD") (pinfunction "26_DD") (pintype "bidirectional"))
      (node (ref "E13") (pin "6") (pinfunction "G1_6") (pintype "input"))
      (node (ref "LASTDEV") (pin "5") (pinfunction "5_5") (pintype "passive"))
    )
    (net (code "19") (name "BMB00") (class "Default")
      (node (ref "D35L1") (pin "D") (pinfunction "4_D") (pintype "bidirectional"))
      (node (ref "D35L2") (pin "D") (pinfunction "4_D") (pintype "bidirectional"))
    )
    (net (code "20") (name "BMB01") (class "Default")
      (node (ref "D35L1") (pin "J") (pinfunction "8_J") (pintype "bidirectional"))
      (node (ref "D35L2") (pin "J") (pinfunction "8_J") (pintype "bidirectional"))
    )
    (net (code "21") (name "BMB02") (class "Default")
      (node (ref "D35L1") (pin "N") (pinfunction "12_N") (pintype "bidirectional"))
      (node (ref "D35L2") (pin "N") (pinfunction "12_N") (pintype "bidirectional"))
    )
    (net (code "22") (name "BMB03") (class "Default")
      (node (ref "D35L1") (pin "X") (pinfunction "20_X") (pintype "bidirectional"))
      (node (ref "D35L2") (pin "X") (pinfunction "20_X") (pintype "bidirectional"))
      (node (ref "E1") (pin "13") (pinfunction "I2_13") (pintype "input"))
    )
    (net (code "23") (name "BMB04") (class "Default")
      (node (ref "D35L1") (pin "FF") (pinfunction "28_FF") (pintype "bidirectional"))
      (node (ref "D35L2") (pin "FF") (pinfunction "28_FF") (pintype "bidirectional"))
      (node (ref "E1") (pin "2") (pinfunction "I1_2") (pintype "input"))
    )
    (net (code "24") (name "BMB05") (class "Default")
      (node (ref "D35L1") (pin "RR") (pinfunction "36_RR") (pintype "bidirectional"))
      (node (ref "D35L2") (pin "RR") (pinfunction "36_RR") (pintype "bidirectional"))
      (node (ref "E1") (pin "1") (pinfunction "I0_1") (pintype "input"))
    )
    (net (code "25") (name "BMB06") (class "Default")
      (node (ref "D35L1") (pin "L") (pinfunction "10_L") (pintype "bidirectional"))
      (node (ref "D35L2") (pin "L") (pinfunction "10_L") (pintype "bidirectional"))
      (node (ref "E14") (pin "3") (pinfunction "C_3") (pintype "input"))
    )
    (net (code "26") (name "BMB07") (class "Default")
      (node (ref "D35L1") (pin "V") (pinfunction "18_V") (pintype "bidirectional"))
      (node (ref "D35L2") (pin "V") (pinfunction "18_V") (pintype "bidirectional"))
      (node (ref "E14") (pin "2") (pinfunction "B_2") (pintype "input"))
    )
    (net (code "27") (name "BMB08") (class "Default")
      (node (ref "D35L1") (pin "DD") (pinfunction "26_DD") (pintype "bidirectional"))
      (node (ref "D35L2") (pin "DD") (pinfunction "26_DD") (pintype "bidirectional"))
      (node (ref "E14") (pin "1") (pinfunction "A_1") (pintype "input"))
    )
    (net (code "28") (name "BMB09") (class "Default")
      (node (ref "D35L1") (pin "JJ") (pinfunction "30_JJ") (pintype "bidirectional"))
      (node (ref "D35L2") (pin "JJ") (pinfunction "30_JJ") (pintype "bidirectional"))
      (node (ref "E11") (pin "3") (pinfunction "C_3") (pintype "input"))
      (node (ref "E12") (pin "3") (pinfunction "C_3") (pintype "input"))
      (node (ref "E13") (pin "3") (pinfunction "C_3") (pintype "input"))
    )
    (net (code "29") (name "BMB10") (class "Default")
      (node (ref "D35L1") (pin "NN") (pinfunction "34_NN") (pintype "bidirectional"))
      (node (ref "D35L2") (pin "NN") (pinfunction "34_NN") (pintype "bidirectional"))
      (node (ref "E11") (pin "2") (pinfunction "B_2") (pintype "input"))
      (node (ref "E12") (pin "2") (pinfunction "B_2") (pintype "input"))
      (node (ref "E13") (pin "2") (pinfunction "B_2") (pintype "input"))
    )
    (net (code "30") (name "BMB11") (class "Default")
      (node (ref "D35L1") (pin "TT") (pinfunction "38_TT") (pintype "bidirectional"))
      (node (ref "D35L2") (pin "TT") (pinfunction "38_TT") (pintype "bidirectional"))
      (node (ref "E11") (pin "1") (pinfunction "A_1") (pintype "input"))
      (node (ref "E12") (pin "1") (pinfunction "A_1") (pintype "input"))
      (node (ref "E13") (pin "1") (pinfunction "A_1") (pintype "input"))
    )
    (net (code "31") (name "BTS1") (class "Default")
      (node (ref "D36L1") (pin "NN") (pinfunction "34_NN") (pintype "bidirectional"))
      (node (ref "D36L2") (pin "NN") (pinfunction "34_NN") (pintype "bidirectional"))
      (node (ref "LASTDEV") (pin "3") (pinfunction "3_3") (pintype "passive"))
    )
    (net (code "32") (name "BTS3") (class "Default")
      (node (ref "D36L1") (pin "JJ") (pinfunction "30_JJ") (pintype "bidirectional"))
      (node (ref "D36L2") (pin "JJ") (pinfunction "30_JJ") (pintype "bidirectional"))
      (node (ref "LASTDEV") (pin "4") (pinfunction "4_4") (pintype "passive"))
    )
    (net (code "33") (name "CLK_BUF") (class "Default")
      (node (ref "E21") (pin "10") (pinfunction "CLK_10") (pintype "input"))
      (node (ref "E22") (pin "10") (pinfunction "CLK_10") (pintype "input"))
      (node (ref "E23") (pin "10") (pinfunction "CLK_10") (pintype "input"))
      (node (ref "E4") (pin "2") (pinfunction "CLK_2") (pintype "input"))
      (node (ref "E5") (pin "6") (pinfunction "O_6") (pintype "output"))
    )
    (net (code "34") (name "DONE") (class "Default")
      (node (ref "E17") (pin "4") (pinfunction "J_4") (pintype "input"))
      (node (ref "E20") (pin "13") (pinfunction "I1_13") (pintype "input"))
      (node (ref "E25") (pin "3") (pinfunction "I_3") (pintype "input"))
      (node (ref "E26") (pin "9") (pinfunction "I0_9") (pintype "input"))
      (node (ref "E31") (pin "10") (pinfunction "I1_10") (pintype "input"))
      (node (ref "E31") (pin "4") (pinfunction "I2_4") (pintype "input"))
      (node (ref "E32") (pin "11") (pinfunction "I2_11") (pintype "input"))
      (node (ref "E36") (pin "10") (pinfunction "O_10") (pintype "output"))
    )
    (net (code "35") (name "DONE_FF") (class "Default")
      (node (ref "E17") (pin "15") (pinfunction "Q_15") (pintype "output"))
      (node (ref "IC10") (pin "6") (pinfunction "I0_6") (pintype "input"))
    )
    (net (code "36") (name "DONE_SKIP") (class "Default")
      (node (ref "E17") (pin "16") (pinfunction "K_16") (pintype "input"))
      (node (ref "E18") (pin "10") (pinfunction "O_10") (pintype "output"))
      (node (ref "E20") (pin "5") (pinfunction "I1_5") (pintype "input"))
      (node (ref "E26") (pin "10") (pinfunction "I1_10") (pintype "input"))
    )
    (net (code "37") (name "ERROR") (class "Default")
      (node (ref "E19") (pin "9") (pinfunction "J_9") (pintype "input"))
      (node (ref "E26") (pin "4") (pinfunction "I0_4") (pintype "input"))
      (node (ref "E36") (pin "1") (pinfunction "O_1") (pintype "output"))
    )
    (net (code "38") (name "ERR_SKIP") (class "Default")
      (node (ref "E18") (pin "4") (pinfunction "O_4") (pintype "output"))
      (node (ref "E19") (pin "12") (pinfunction "K_12") (pintype "input"))
      (node (ref "E20") (pin "4") (pinfunction "I0_4") (pintype "input"))
      (node (ref "E26") (pin "5") (pinfunction "I1_5") (pintype "input"))
    )
    (net (code "39") (name "GND") (class "Default")
      (node (ref "C1") (pin "2") (pinfunction "2_2") (pintype "passive"))
      (node (ref "C10") (pin "2") (pinfunction "2_2") (pintype "passive"))
      (node (ref "C11") (pin "2") (pinfunction "2_2") (pintype "passive"))
      (node (ref "C12") (pin "2") (pinfunction "2_2") (pintype "passive"))
      (node (ref "C13") (pin "2") (pinfunction "2_2") (pintype "passive"))
      (node (ref "C14") (pin "2") (pinfunction "2_2") (pintype "passive"))
      (node (ref "C15") (pin "2") (pinfunction "2_2") (pintype "passive"))
      (node (ref "C16") (pin "2") (pinfunction "2_2") (pintype "passive"))
      (node (ref "C17") (pin "2") (pinfunction "2_2") (pintype "passive"))
      (node (ref "C18") (pin "2") (pinfunction "2_2") (pintype "passive"))
      (node (ref "C19") (pin "2") (pinfunction "2_2") (pintype "passive"))
      (node (ref "C2") (pin "2") (pinfunction "2_2") (pintype "passive"))
      (node (ref "C20") (pin "2") (pinfunction "2_2") (pintype "passive"))
      (node (ref "C21") (pin "2") (pinfunction "2_2") (pintype "passive"))
      (node (ref "C22") (pin "2") (pinfunction "2_2") (pintype "passive"))
      (node (ref "C23") (pin "2") (pinfunction "2_2") (pintype "passive"))
      (node (ref "C24") (pin "2") (pinfunction "2_2") (pintype "passive"))
      (node (ref "C25") (pin "2") (pinfunction "2_2") (pintype "passive"))
      (node (ref "C26") (pin "2") (pinfunction "2_2") (pintype "passive"))
      (node (ref "C27") (pin "2") (pinfunction "2_2") (pintype "passive"))
      (node (ref "C28") (pin "2") (pinfunction "2_2") (pintype "passive"))
      (node (ref "C29") (pin "2") (pinfunction "2_2") (pintype "passive"))
      (node (ref "C3") (pin "2") (pinfunction "2_2") (pintype "passive"))
      (node (ref "C30") (pin "2") (pinfunction "2_2") (pintype "passive"))
      (node (ref "C31") (pin "2") (pinfunction "2_2") (pintype "passive"))
      (node (ref "C32") (pin "2") (pinfunction "2_2") (pintype "passive"))
      (node (ref "C33") (pin "2") (pinfunction "2_2") (pintype "passive"))
      (node (ref "C34") (pin "2") (pinfunction "2_2") (pintype "passive"))
      (node (ref "C35") (pin "2") (pinfunction "2_2") (pintype "passive"))
      (node (ref "C36") (pin "2") (pinfunction "2_2") (pintype "passive"))
      (node (ref "C37") (pin "2") (pinfunction "2_2") (pintype "passive"))
      (node (ref "C38") (pin "2") (pinfunction "2_2") (pintype "passive"))
      (node (ref "C39") (pin "2") (pinfunction "2_2") (pintype "passive"))
      (node (ref "C4") (pin "2") (pinfunction "2_2") (pintype "passive"))
      (node (ref "C40") (pin "-") (pinfunction "-_-") (pintype "passive"))
      (node (ref "C5") (pin "2") (pinfunction "2_2") (pintype "passive"))
      (node (ref "C6") (pin "2") (pinfunction "2_2") (pintype "passive"))
      (node (ref "C7") (pin "2") (pinfunction "2_2") (pintype "passive"))
      (node (ref "C8") (pin "2") (pinfunction "2_2") (pintype "passive"))
      (node (ref "C9") (pin "2") (pinfunction "2_2") (pintype "passive"))
      (node (ref "D34L1") (pin "A") (pinfunction "1_A") (pintype "bidirectional"))
      (node (ref "D34L1") (pin "AA") (pinfunction "23_AA") (pintype "bidirectional"))
      (node (ref "D34L1") (pin "C") (pinfunction "3_C") (pintype "bidirectional"))
      (node (ref "D34L1") (pin "CC") (pinfunction "25_CC") (pintype "bidirectional"))
      (node (ref "D34L1") (pin "E") (pinfunction "5_E") (pintype "bidirectional"))
      (node (ref "D34L1") (pin "EE") (pinfunction "27_EE") (pintype "bidirectional"))
      (node (ref "D34L1") (pin "H") (pinfunction "7_H") (pintype "bidirectional"))
      (node (ref "D34L1") (pin "HH") (pinfunction "29_HH") (pintype "bidirectional"))
      (node (ref "D34L1") (pin "K") (pinfunction "9_K") (pintype "bidirectional"))
      (node (ref "D34L1") (pin "KK") (pinfunction "31_KK") (pintype "bidirectional"))
      (node (ref "D34L1") (pin "M") (pinfunction "11_M") (pintype "bidirectional"))
      (node (ref "D34L1") (pin "MM") (pinfunction "33_MM") (pintype "bidirectional"))
      (node (ref "D34L1") (pin "P") (pinfunction "13_P") (pintype "bidirectional"))
      (node (ref "D34L1") (pin "PP") (pinfunction "35_PP") (pintype "bidirectional"))
      (node (ref "D34L1") (pin "S") (pinfunction "15_S") (pintype "bidirectional"))
      (node (ref "D34L1") (pin "SS") (pinfunction "37_SS") (pintype "bidirectional"))
      (node (ref "D34L1") (pin "U") (pinfunction "17_U") (pintype "bidirectional"))
      (node (ref "D34L1") (pin "UU") (pinfunction "39_UU") (pintype "bidirectional"))
      (node (ref "D34L1") (pin "W") (pinfunction "19_W") (pintype "bidirectional"))
      (node (ref "D34L1") (pin "Y") (pinfunction "21_Y") (pintype "bidirectional"))
      (node (ref "D34L2") (pin "A") (pinfunction "1_A") (pintype "bidirectional"))
      (node (ref "D34L2") (pin "AA") (pinfunction "23_AA") (pintype "bidirectional"))
      (node (ref "D34L2") (pin "C") (pinfunction "3_C") (pintype "bidirectional"))
      (node (ref "D34L2") (pin "CC") (pinfunction "25_CC") (pintype "bidirectional"))
      (node (ref "D34L2") (pin "E") (pinfunction "5_E") (pintype "bidirectional"))
      (node (ref "D34L2") (pin "EE") (pinfunction "27_EE") (pintype "bidirectional"))
      (node (ref "D34L2") (pin "H") (pinfunction "7_H") (pintype "bidirectional"))
      (node (ref "D34L2") (pin "HH") (pinfunction "29_HH") (pintype "bidirectional"))
      (node (ref "D34L2") (pin "K") (pinfunction "9_K") (pintype "bidirectional"))
      (node (ref "D34L2") (pin "KK") (pinfunction "31_KK") (pintype "bidirectional"))
      (node (ref "D34L2") (pin "M") (pinfunction "11_M") (pintype "bidirectional"))
      (node (ref "D34L2") (pin "MM") (pinfunction "33_MM") (pintype "bidirectional"))
      (node (ref "D34L2") (pin "P") (pinfunction "13_P") (pintype "bidirectional"))
      (node (ref "D34L2") (pin "PP") (pinfunction "35_PP") (pintype "bidirectional"))
      (node (ref "D34L2") (pin "S") (pinfunction "15_S") (pintype "bidirectional"))
      (node (ref "D34L2") (pin "SS") (pinfunction "37_SS") (pintype "bidirectional"))
      (node (ref "D34L2") (pin "U") (pinfunction "17_U") (pintype "bidirectional"))
      (node (ref "D34L2") (pin "UU") (pinfunction "39_UU") (pintype "bidirectional"))
      (node (ref "D34L2") (pin "W") (pinfunction "19_W") (pintype "bidirectional"))
      (node (ref "D34L2") (pin "Y") (pinfunction "21_Y") (pintype "bidirectional"))
      (node (ref "D35L1") (pin "A") (pinfunction "1_A") (pintype "bidirectional"))
      (node (ref "D35L1") (pin "AA") (pinfunction "23_AA") (pintype "bidirectional"))
      (node (ref "D35L1") (pin "C") (pinfunction "3_C") (pintype "bidirectional"))
      (node (ref "D35L1") (pin "CC") (pinfunction "25_CC") (pintype "bidirectional"))
      (node (ref "D35L1") (pin "E") (pinfunction "5_E") (pintype "bidirectional"))
      (node (ref "D35L1") (pin "EE") (pinfunction "27_EE") (pintype "bidirectional"))
      (node (ref "D35L1") (pin "H") (pinfunction "7_H") (pintype "bidirectional"))
      (node (ref "D35L1") (pin "HH") (pinfunction "29_HH") (pintype "bidirectional"))
      (node (ref "D35L1") (pin "K") (pinfunction "9_K") (pintype "bidirectional"))
      (node (ref "D35L1") (pin "KK") (pinfunction "31_KK") (pintype "bidirectional"))
      (node (ref "D35L1") (pin "M") (pinfunction "11_M") (pintype "bidirectional"))
      (node (ref "D35L1") (pin "MM") (pinfunction "33_MM") (pintype "bidirectional"))
      (node (ref "D35L1") (pin "P") (pinfunction "13_P") (pintype "bidirectional"))
      (node (ref "D35L1") (pin "PP") (pinfunction "35_PP") (pintype "bidirectional"))
      (node (ref "D35L1") (pin "S") (pinfunction "15_S") (pintype "bidirectional"))
      (node (ref "D35L1") (pin "SS") (pinfunction "37_SS") (pintype "bidirectional"))
      (node (ref "D35L1") (pin "U") (pinfunction "17_U") (pintype "bidirectional"))
      (node (ref "D35L1") (pin "UU") (pinfunction "39_UU") (pintype "bidirectional"))
      (node (ref "D35L1") (pin "W") (pinfunction "19_W") (pintype "bidirectional"))
      (node (ref "D35L1") (pin "Y") (pinfunction "21_Y") (pintype "bidirectional"))
      (node (ref "D35L2") (pin "A") (pinfunction "1_A") (pintype "bidirectional"))
      (node (ref "D35L2") (pin "AA") (pinfunction "23_AA") (pintype "bidirectional"))
      (node (ref "D35L2") (pin "C") (pinfunction "3_C") (pintype "bidirectional"))
      (node (ref "D35L2") (pin "CC") (pinfunction "25_CC") (pintype "bidirectional"))
      (node (ref "D35L2") (pin "E") (pinfunction "5_E") (pintype "bidirectional"))
      (node (ref "D35L2") (pin "EE") (pinfunction "27_EE") (pintype "bidirectional"))
      (node (ref "D35L2") (pin "H") (pinfunction "7_H") (pintype "bidirectional"))
      (node (ref "D35L2") (pin "HH") (pinfunction "29_HH") (pintype "bidirectional"))
      (node (ref "D35L2") (pin "K") (pinfunction "9_K") (pintype "bidirectional"))
      (node (ref "D35L2") (pin "KK") (pinfunction "31_KK") (pintype "bidirectional"))
      (node (ref "D35L2") (pin "M") (pinfunction "11_M") (pintype "bidirectional"))
      (node (ref "D35L2") (pin "MM") (pinfunction "33_MM") (pintype "bidirectional"))
      (node (ref "D35L2") (pin "P") (pinfunction "13_P") (pintype "bidirectional"))
      (node (ref "D35L2") (pin "PP") (pinfunction "35_PP") (pintype "bidirectional"))
      (node (ref "D35L2") (pin "S") (pinfunction "15_S") (pintype "bidirectional"))
      (node (ref "D35L2") (pin "SS") (pinfunction "37_SS") (pintype "bidirectional"))
      (node (ref "D35L2") (pin "U") (pinfunction "17_U") (pintype "bidirectional"))
      (node (ref "D35L2") (pin "UU") (pinfunction "39_UU") (pintype "bidirectional"))
      (node (ref "D35L2") (pin "W") (pinfunction "19_W") (pintype "bidirectional"))
      (node (ref "D35L2") (pin "Y") (pinfunction "21_Y") (pintype "bidirectional"))
      (node (ref "D36L1") (pin "A") (pinfunction "1_A") (pintype "bidirectional"))
      (node (ref "D36L1") (pin "AA") (pinfunction "23_AA") (pintype "bidirectional"))
      (node (ref "D36L1") (pin "C") (pinfunction "3_C") (pintype "bidirectional"))
      (node (ref "D36L1") (pin "CC") (pinfunction "25_CC") (pintype "bidirectional"))
      (node (ref "D36L1") (pin "E") (pinfunction "5_E") (pintype "bidirectional"))
      (node (ref "D36L1") (pin "EE") (pinfunction "27_EE") (pintype "bidirectional"))
      (node (ref "D36L1") (pin "H") (pinfunction "7_H") (pintype "bidirectional"))
      (node (ref "D36L1") (pin "HH") (pinfunction "29_HH") (pintype "bidirectional"))
      (node (ref "D36L1") (pin "K") (pinfunction "9_K") (pintype "bidirectional"))
      (node (ref "D36L1") (pin "KK") (pinfunction "31_KK") (pintype "bidirectional"))
      (node (ref "D36L1") (pin "M") (pinfunction "11_M") (pintype "bidirectional"))
      (node (ref "D36L1") (pin "MM") (pinfunction "33_MM") (pintype "bidirectional"))
      (node (ref "D36L1") (pin "P") (pinfunction "13_P") (pintype "bidirectional"))
      (node (ref "D36L1") (pin "PP") (pinfunction "35_PP") (pintype "bidirectional"))
      (node (ref "D36L1") (pin "S") (pinfunction "15_S") (pintype "bidirectional"))
      (node (ref "D36L1") (pin "SS") (pinfunction "37_SS") (pintype "bidirectional"))
      (node (ref "D36L1") (pin "U") (pinfunction "17_U") (pintype "bidirectional"))
      (node (ref "D36L1") (pin "UU") (pinfunction "39_UU") (pintype "bidirectional"))
      (node (ref "D36L1") (pin "W") (pinfunction "19_W") (pintype "bidirectional"))
      (node (ref "D36L1") (pin "Y") (pinfunction "21_Y") (pintype "bidirectional"))
      (node (ref "D36L2") (pin "A") (pinfunction "1_A") (pintype "bidirectional"))
      (node (ref "D36L2") (pin "AA") (pinfunction "23_AA") (pintype "bidirectional"))
      (node (ref "D36L2") (pin "C") (pinfunction "3_C") (pintype "bidirectional"))
      (node (ref "D36L2") (pin "CC") (pinfunction "25_CC") (pintype "bidirectional"))
      (node (ref "D36L2") (pin "E") (pinfunction "5_E") (pintype "bidirectional"))
      (node (ref "D36L2") (pin "EE") (pinfunction "27_EE") (pintype "bidirectional"))
      (node (ref "D36L2") (pin "H") (pinfunction "7_H") (pintype "bidirectional"))
      (node (ref "D36L2") (pin "HH") (pinfunction "29_HH") (pintype "bidirectional"))
      (node (ref "D36L2") (pin "K") (pinfunction "9_K") (pintype "bidirectional"))
      (node (ref "D36L2") (pin "KK") (pinfunction "31_KK") (pintype "bidirectional"))
      (node (ref "D36L2") (pin "M") (pinfunction "11_M") (pintype "bidirectional"))
      (node (ref "D36L2") (pin "MM") (pinfunction "33_MM") (pintype "bidirectional"))
      (node (ref "D36L2") (pin "P") (pinfunction "13_P") (pintype "bidirectional"))
      (node (ref "D36L2") (pin "PP") (pinfunction "35_PP") (pintype "bidirectional"))
      (node (ref "D36L2") (pin "S") (pinfunction "15_S") (pintype "bidirectional"))
      (node (ref "D36L2") (pin "SS") (pinfunction "37_SS") (pintype "bidirectional"))
      (node (ref "D36L2") (pin "U") (pinfunction "17_U") (pintype "bidirectional"))
      (node (ref "D36L2") (pin "UU") (pinfunction "39_UU") (pintype "bidirectional"))
      (node (ref "D36L2") (pin "W") (pinfunction "19_W") (pintype "bidirectional"))
      (node (ref "D36L2") (pin "Y") (pinfunction "21_Y") (pintype "bidirectional"))
      (node (ref "DRIVE") (pin "A") (pinfunction "1_A") (pintype "bidirectional"))
      (node (ref "DRIVE") (pin "AA") (pinfunction "23_AA") (pintype "bidirectional"))
      (node (ref "DRIVE") (pin "B") (pinfunction "2_B") (pintype "bidirectional"))
      (node (ref "DRIVE") (pin "C") (pinfunction "3_C") (pintype "bidirectional"))
      (node (ref "DRIVE") (pin "CC") (pinfunction "25_CC") (pintype "bidirectional"))
      (node (ref "DRIVE") (pin "DD") (pinfunction "26_DD") (pintype "bidirectional"))
      (node (ref "DRIVE") (pin "E") (pinfunction "5_E") (pintype "bidirectional"))
      (node (ref "DRIVE") (pin "EE") (pinfunction "27_EE") (pintype "bidirectional"))
      (node (ref "DRIVE") (pin "F") (pinfunction "6_F") (pintype "bidirectional"))
      (node (ref "DRIVE") (pin "H") (pinfunction "7_H") (pintype "bidirectional"))
      (node (ref "DRIVE") (pin "HH") (pinfunction "29_HH") (pintype "bidirectional"))
      (node (ref "DRIVE") (pin "JJ") (pinfunction "30_JJ") (pintype "bidirectional"))
      (node (ref "DRIVE") (pin "K") (pinfunction "9_K") (pintype "bidirectional"))
      (node (ref "DRIVE") (pin "KK") (pinfunction "31_KK") (pintype "bidirectional"))
      (node (ref "DRIVE") (pin "L") (pinfunction "10_L") (pintype "bidirectional"))
      (node (ref "DRIVE") (pin "M") (pinfunction "11_M") (pintype "bidirectional"))
      (node (ref "DRIVE") (pin "MM") (pinfunction "33_MM") (pintype "bidirectional"))
      (node (ref "DRIVE") (pin "NN") (pinfunction "34_NN") (pintype "bidirectional"))
      (node (ref "DRIVE") (pin "P") (pinfunction "13_P") (pintype "bidirectional"))
      (node (ref "DRIVE") (pin "PP") (pinfunction "35_PP") (pintype "bidirectional"))
      (node (ref "DRIVE") (pin "R") (pinfunction "14_R") (pintype "bidirectional"))
      (node (ref "DRIVE") (pin "S") (pinfunction "15_S") (pintype "bidirectional"))
      (node (ref "DRIVE") (pin "SS") (pinfunction "37_SS") (pintype "bidirectional"))
      (node (ref "DRIVE") (pin "TT") (pinfunction "38_TT") (pintype "bidirectional"))
      (node (ref "DRIVE") (pin "U") (pinfunction "17_U") (pintype "bidirectional"))
      (node (ref "DRIVE") (pin "UU") (pinfunction "39_UU") (pintype "bidirectional"))
      (node (ref "DRIVE") (pin "V") (pinfunction "18_V") (pintype "bidirectional"))
      (node (ref "DRIVE") (pin "VV") (pinfunction "40_VV") (pintype "bidirectional"))
      (node (ref "DRIVE") (pin "W") (pinfunction "19_W") (pintype "bidirectional"))
      (node (ref "DRIVE") (pin "Y") (pinfunction "21_Y") (pintype "bidirectional"))
      (node (ref "DRIVE") (pin "Z") (pinfunction "22_Z") (pintype "bidirectional"))
      (node (ref "E1") (pin "4") (pinfunction "I1_4") (pintype "input"))
      (node (ref "E1") (pin "5") (pinfunction "I2_5") (pintype "input"))
      (node (ref "E11") (pin "5") (pinfunction "G2B_5") (pintype "input"))
      (node (ref "E12") (pin "5") (pinfunction "G2B_5") (pintype "input"))
      (node (ref "E13") (pin "5") (pinfunction "G2B_5") (pintype "input"))
      (node (ref "E2") (pin "2") (pinfunction "D_2") (pintype "input"))
      (node (ref "E4") (pin "6") (pinfunction "D_6") (pintype "input"))
      (node (ref "LASTDEV") (pin "1") (pinfunction "1_1") (pintype "passive"))
      (node (ref "R10") (pin "1") (pinfunction "1_1") (pintype "passive"))
      (node (ref "R11") (pin "1") (pinfunction "1_1") (pintype "passive"))
      (node (ref "R12") (pin "1") (pinfunction "1_1") (pintype "passive"))
      (node (ref "R13") (pin "1") (pinfunction "1_1") (pintype "passive"))
      (node (ref "R14") (pin "1") (pinfunction "1_1") (pintype "passive"))
      (node (ref "R15") (pin "1") (pinfunction "1_1") (pintype "passive"))
      (node (ref "R16") (pin "1") (pinfunction "1_1") (pintype "passive"))
      (node (ref "R17") (pin "1") (pinfunction "1_1") (pintype "passive"))
      (node (ref "SL1") (pin "2") (pinfunction "S_2") (pintype "passive"))
      (node (ref "SL1") (pin "3") (pinfunction "S_3") (pintype "passive"))
    )
    (net (code "40") (name "INIT") (class "Default")
      (node (ref "E1") (pin "8") (pinfunction "O_8") (pintype "output"))
      (node (ref "E15") (pin "4") (pinfunction "I0_4") (pintype "input"))
      (node (ref "E15") (pin "5") (pinfunction "I1_5") (pintype "input"))
      (node (ref "E18") (pin "12") (pinfunction "I1_12") (pintype "input"))
      (node (ref "IC8") (pin "6") (pinfunction "I0_6") (pintype "input"))
      (node (ref "IC8") (pin "7") (pinfunction "I1_7") (pintype "input"))
    )
    (net (code "41") (name "MAINT") (class "Default")
      (node (ref "E16") (pin "9") (pinfunction "Q_9") (pintype "output"))
      (node (ref "E32") (pin "9") (pinfunction "I0_9") (pintype "input"))
      (node (ref "E35") (pin "3") (pinfunction "I1_3") (pintype "input"))
      (node (ref "E35") (pin "6") (pinfunction "I1_6") (pintype "input"))
      (node (ref "E35") (pin "9") (pinfunction "I1_9") (pintype "input"))
      (node (ref "E36") (pin "2") (pinfunction "I0_2") (pintype "input"))
      (node (ref "E36") (pin "6") (pinfunction "I1_6") (pintype "input"))
      (node (ref "E36") (pin "9") (pinfunction "I1_9") (pintype "input"))
    )
    (net (code "42") (name "MSB8") (class "Default")
      (node (ref "E21") (pin "12") (pinfunction "QD_12") (pintype "output"))
      (node (ref "E23") (pin "2") (pinfunction "J_2") (pintype "input"))
      (node (ref "E23") (pin "3") (pinfunction "K_3") (pintype "input"))
      (node (ref "E8") (pin "5") (pinfunction "I2_5") (pintype "input"))
      (node (ref "IC1") (pin "6") (pinfunction "I0_6") (pintype "input"))
    )
    (net (code "43") (name "MSB12") (class "Default")
      (node (ref "E23") (pin "12") (pinfunction "QD_12") (pintype "output"))
      (node (ref "E8") (pin "2") (pinfunction "I1_2") (pintype "input"))
      (node (ref "IC6") (pin "1") (pinfunction "I0_1") (pintype "input"))
    )
    (net (code "44") (name "Net-(70-P)") (class "Default")
      (node (ref "70") (pin "1") (pinfunction "P_1") (pintype "passive"))
      (node (ref "E14") (pin "15") (pinfunction "Y0_15") (pintype "output"))
    )
    (net (code "45") (name "Net-(71-P)") (class "Default")
      (node (ref "71") (pin "1") (pinfunction "P_1") (pintype "passive"))
      (node (ref "E14") (pin "14") (pinfunction "Y1_14") (pintype "output"))
    )
    (net (code "46") (name "Net-(72-P)") (class "Default")
      (node (ref "72") (pin "1") (pinfunction "P_1") (pintype "passive"))
      (node (ref "E14") (pin "13") (pinfunction "Y2_13") (pintype "output"))
    )
    (net (code "47") (name "Net-(73-P)") (class "Default")
      (node (ref "73") (pin "1") (pinfunction "P_1") (pintype "passive"))
      (node (ref "E14") (pin "12") (pinfunction "Y3_12") (pintype "output"))
    )
    (net (code "48") (name "Net-(74-P)") (class "Default")
      (node (ref "74") (pin "1") (pinfunction "P_1") (pintype "passive"))
      (node (ref "E14") (pin "11") (pinfunction "Y4_11") (pintype "output"))
    )
    (net (code "49") (name "Net-(75-P)") (class "Default")
      (node (ref "75") (pin "1") (pinfunction "P_1") (pintype "passive"))
      (node (ref "E14") (pin "10") (pinfunction "Y5_10") (pintype "output"))
    )
    (net (code "50") (name "Net-(76-P)") (class "Default")
      (node (ref "76") (pin "1") (pinfunction "P_1") (pintype "passive"))
      (node (ref "E14") (pin "9") (pinfunction "Y6_9") (pintype "output"))
    )
    (net (code "51") (name "Net-(77-P)") (class "Default")
      (node (ref "77") (pin "1") (pinfunction "P_1") (pintype "passive"))
      (node (ref "E14") (pin "7") (pinfunction "Y7_7") (pintype "output"))
    )
    (net (code "52") (name "Net-(E1B-O)") (class "Default")
      (node (ref "E1") (pin "10") (pinfunction "I1_10") (pintype "input"))
      (node (ref "E1") (pin "6") (pinfunction "O_6") (pintype "output"))
      (node (ref "E1") (pin "9") (pinfunction "I0_9") (pintype "input"))
    )
    (net (code "53") (name "Net-(E1C-I2)") (class "Default")
      (node (ref "E1") (pin "11") (pinfunction "I2_11") (pintype "input"))
      (node (ref "E2") (pin "6") (pinfunction "~{Q}_6") (pintype "output"))
    )
    (net (code "54") (name "Net-(E4A-A)") (class "Default")
      (node (ref "E4") (pin "10") (pinfunction "ENT_10") (pintype "input"))
      (node (ref "E4") (pin "3") (pinfunction "A_3") (pintype "input"))
      (node (ref "E4") (pin "4") (pinfunction "B_4") (pintype "input"))
      (node (ref "E4") (pin "7") (pinfunction "ENP_7") (pintype "input"))
      (node (ref "R19") (pin "2") (pinfunction "2_2") (pintype "passive"))
    )
    (net (code "55") (name "Net-(E4A-C)") (class "Default")
      (node (ref "E4") (pin "5") (pinfunction "C_5") (pintype "input"))
      (node (ref "E5") (pin "3") (pinfunction "O_3") (pintype "output"))
    )
    (net (code "56") (name "Net-(E5A-I0)") (class "Default")
      (node (ref "E5") (pin "1") (pinfunction "I0_1") (pintype "input"))
      (node (ref "E5") (pin "11") (pinfunction "O_11") (pintype "output"))
    )
    (net (code "57") (name "Net-(E8A-O)") (class "Default")
      (node (ref "E8") (pin "11") (pinfunction "I2_11") (pintype "input"))
      (node (ref "E8") (pin "12") (pinfunction "O_12") (pintype "output"))
    )
    (net (code "58") (name "Net-(E8B-O)") (class "Default")
      (node (ref "E8") (pin "6") (pinfunction "O_6") (pintype "output"))
      (node (ref "E8") (pin "9") (pinfunction "I0_9") (pintype "input"))
    )
    (net (code "59") (name "Net-(E10A-I0)") (class "Default")
      (node (ref "E10") (pin "1") (pinfunction "I0_1") (pintype "input"))
      (node (ref "E10") (pin "6") (pinfunction "O_6") (pintype "output"))
    )
    (net (code "60") (name "Net-(E10A-O)") (class "Default")
      (node (ref "E10") (pin "10") (pinfunction "I1_10") (pintype "input"))
      (node (ref "E10") (pin "11") (pinfunction "I2_11") (pintype "input"))
      (node (ref "E10") (pin "12") (pinfunction "O_12") (pintype "output"))
    )
    (net (code "61") (name "Net-(E10C-O)") (class "Default")
      (node (ref "E10") (pin "8") (pinfunction "O_8") (pintype "output"))
      (node (ref "IC7") (pin "1") (pinfunction "I0_1") (pintype "input"))
      (node (ref "IC7") (pin "2") (pinfunction "I1_2") (pintype "input"))
    )
    (net (code "62") (name "Net-(E14A-G2A)") (class "Default")
      (node (ref "E1") (pin "12") (pinfunction "O_12") (pintype "output"))
      (node (ref "E14") (pin "4") (pinfunction "G2A_4") (pintype "input"))
      (node (ref "E14") (pin "5") (pinfunction "G2B_5") (pintype "input"))
    )
    (net (code "63") (name "Net-(E15A-O)") (class "Default")
      (node (ref "E15") (pin "3") (pinfunction "O_3") (pintype "output"))
      (node (ref "E8") (pin "13") (pinfunction "I2_13") (pintype "input"))
      (node (ref "E8") (pin "3") (pinfunction "I0_3") (pintype "input"))
    )
    (net (code "64") (name "Net-(E15C-I0)") (class "Default")
      (node (ref "E15") (pin "9") (pinfunction "I0_9") (pintype "input"))
      (node (ref "E20") (pin "11") (pinfunction "O_11") (pintype "output"))
      (node (ref "E24") (pin "10") (pinfunction "I1_10") (pintype "input"))
    )
    (net (code "65") (name "Net-(E15C-O)") (class "Default")
      (node (ref "E15") (pin "8") (pinfunction "O_8") (pintype "output"))
      (node (ref "E24") (pin "12") (pinfunction "I0_12") (pintype "input"))
    )
    (net (code "66") (name "Net-(E15D-O)") (class "Default")
      (node (ref "E15") (pin "11") (pinfunction "O_11") (pintype "output"))
      (node (ref "E8") (pin "10") (pinfunction "I1_10") (pintype "input"))
    )
    (net (code "67") (name "Net-(E17A-CLK)") (class "Default")
      (node (ref "E17") (pin "1") (pinfunction "CLK_1") (pintype "input"))
      (node (ref "E26") (pin "8") (pinfunction "O_8") (pintype "output"))
    )
    (net (code "68") (name "Net-(E17A-~{Q})") (class "Default")
      (node (ref "E17") (pin "14") (pinfunction "~{Q}_14") (pintype "output"))
      (node (ref "E18") (pin "9") (pinfunction "I1_9") (pintype "input"))
    )
    (net (code "69") (name "Net-(E17B-CLR)") (class "Default")
      (node (ref "E17") (pin "8") (pinfunction "CLR_8") (pintype "input"))
      (node (ref "E18") (pin "13") (pinfunction "O_13") (pintype "output"))
    )
    (net (code "70") (name "Net-(E17B-J)") (class "Default")
      (node (ref "E17") (pin "12") (pinfunction "K_12") (pintype "input"))
      (node (ref "E17") (pin "9") (pinfunction "J_9") (pintype "input"))
      (node (ref "E8") (pin "8") (pinfunction "O_8") (pintype "output"))
      (node (ref "IC7") (pin "7") (pinfunction "I1_7") (pintype "input"))
    )
    (net (code "71") (name "Net-(E18A-I1)") (class "Default")
      (node (ref "E18") (pin "3") (pinfunction "I1_3") (pintype "input"))
      (node (ref "E19") (pin "14") (pinfunction "~{Q}_14") (pintype "output"))
    )
    (net (code "72") (name "Net-(E18B-I1)") (class "Default")
      (node (ref "E18") (pin "6") (pinfunction "I1_6") (pintype "input"))
      (node (ref "E19") (pin "10") (pinfunction "~{Q}_10") (pintype "output"))
    )
    (net (code "73") (name "Net-(E19A-CLK)") (class "Default")
      (node (ref "E19") (pin "1") (pinfunction "CLK_1") (pintype "input"))
      (node (ref "E26") (pin "3") (pinfunction "O_3") (pintype "output"))
    )
    (net (code "74") (name "Net-(E19B-CLK)") (class "Default")
      (node (ref "E19") (pin "6") (pinfunction "CLK_6") (pintype "input"))
      (node (ref "E26") (pin "6") (pinfunction "O_6") (pintype "output"))
    )
    (net (code "75") (name "Net-(E20A-I1)") (class "Default")
      (node (ref "E20") (pin "2") (pinfunction "I1_2") (pintype "input"))
      (node (ref "E20") (pin "6") (pinfunction "O_6") (pintype "output"))
    )
    (net (code "76") (name "Net-(E20A-O)") (class "Default")
      (node (ref "E20") (pin "3") (pinfunction "O_3") (pintype "output"))
      (node (ref "IC10") (pin "1") (pinfunction "I0_1") (pintype "input"))
      (node (ref "IC10") (pin "2") (pinfunction "I1_2") (pintype "input"))
    )
    (net (code "77") (name "Net-(E21A-J)") (class "Default")
      (node (ref "E21") (pin "2") (pinfunction "J_2") (pintype "input"))
      (node (ref "E21") (pin "3") (pinfunction "K_3") (pintype "input"))
      (node (ref "E22") (pin "12") (pinfunction "QD_12") (pintype "output"))
      (node (ref "IC4") (pin "6") (pinfunction "I0_6") (pintype "input"))
    )
    (net (code "78") (name "Net-(E21A-QA)") (class "Default")
      (node (ref "E21") (pin "15") (pinfunction "QA_15") (pintype "output"))
      (node (ref "IC3") (pin "6") (pinfunction "I0_6") (pintype "input"))
    )
    (net (code "79") (name "Net-(E21A-QB)") (class "Default")
      (node (ref "E21") (pin "14") (pinfunction "QB_14") (pintype "output"))
      (node (ref "IC3") (pin "1") (pinfunction "I0_1") (pintype "input"))
    )
    (net (code "80") (name "Net-(E21A-QC)") (class "Default")
      (node (ref "E21") (pin "13") (pinfunction "QC_13") (pintype "output"))
      (node (ref "IC4") (pin "1") (pinfunction "I0_1") (pintype "input"))
    )
    (net (code "81") (name "Net-(E22A-QA)") (class "Default")
      (node (ref "E22") (pin "15") (pinfunction "QA_15") (pintype "output"))
      (node (ref "IC2") (pin "1") (pinfunction "I0_1") (pintype "input"))
    )
    (net (code "82") (name "Net-(E22A-QB)") (class "Default")
      (node (ref "E22") (pin "14") (pinfunction "QB_14") (pintype "output"))
      (node (ref "IC5") (pin "6") (pinfunction "I0_6") (pintype "input"))
    )
    (net (code "83") (name "Net-(E22A-QC)") (class "Default")
      (node (ref "E22") (pin "13") (pinfunction "QC_13") (pintype "output"))
      (node (ref "IC5") (pin "1") (pinfunction "I0_1") (pintype "input"))
    )
    (net (code "84") (name "Net-(E23A-QA)") (class "Default")
      (node (ref "E23") (pin "15") (pinfunction "QA_15") (pintype "output"))
      (node (ref "IC2") (pin "6") (pinfunction "I0_6") (pintype "input"))
    )
    (net (code "85") (name "Net-(E23A-QB)") (class "Default")
      (node (ref "E23") (pin "14") (pinfunction "QB_14") (pintype "output"))
      (node (ref "IC1") (pin "1") (pinfunction "I0_1") (pintype "input"))
    )
    (net (code "86") (name "Net-(E23A-QC)") (class "Default")
      (node (ref "E23") (pin "13") (pinfunction "QC_13") (pintype "output"))
      (node (ref "IC6") (pin "6") (pinfunction "I0_6") (pintype "input"))
    )
    (net (code "87") (name "Net-(E24A-I1)") (class "Default")
      (node (ref "E24") (pin "2") (pinfunction "I1_2") (pintype "input"))
      (node (ref "E35") (pin "13") (pinfunction "O_13") (pintype "output"))
      (node (ref "IC1") (pin "7") (pinfunction "I1_7") (pintype "input"))
      (node (ref "IC2") (pin "2") (pinfunction "I1_2") (pintype "input"))
      (node (ref "IC3") (pin "2") (pinfunction "I1_2") (pintype "input"))
      (node (ref "IC3") (pin "7") (pinfunction "I1_7") (pintype "input"))
      (node (ref "IC4") (pin "2") (pinfunction "I1_2") (pintype "input"))
      (node (ref "IC4") (pin "7") (pinfunction "I1_7") (pintype "input"))
      (node (ref "IC5") (pin "2") (pinfunction "I1_2") (pintype "input"))
      (node (ref "IC5") (pin "7") (pinfunction "I1_7") (pintype "input"))
    )
    (net (code "88") (name "Net-(E24A-O)") (class "Default")
      (node (ref "E24") (pin "3") (pinfunction "O_3") (pintype "output"))
      (node (ref "IC1") (pin "2") (pinfunction "I1_2") (pintype "input"))
      (node (ref "IC2") (pin "7") (pinfunction "I1_7") (pintype "input"))
      (node (ref "IC6") (pin "2") (pinfunction "I1_2") (pintype "input"))
      (node (ref "IC6") (pin "7") (pinfunction "I1_7") (pintype "input"))
    )
    (net (code "89") (name "Net-(E24B-O)") (class "Default")
      (node (ref "E24") (pin "6") (pinfunction "O_6") (pintype "output"))
      (node (ref "E32") (pin "1") (pinfunction "I0_1") (pintype "input"))
    )
    (net (code "90") (name "Net-(E24C-O)") (class "Default")
      (node (ref "E24") (pin "8") (pinfunction "O_8") (pintype "output"))
      (node (ref "E30") (pin "13") (pinfunction "CLR_13") (pintype "input"))
    )
    (net (code "91") (name "Net-(E25C-O)") (class "Default")
      (node (ref "E25") (pin "6") (pinfunction "O_6") (pintype "output"))
      (node (ref "E31") (pin "1") (pinfunction "I0_1") (pintype "input"))
      (node (ref "E31") (pin "2") (pinfunction "I1_2") (pintype "input"))
    )
    (net (code "92") (name "Net-(E25D-O)") (class "Default")
      (node (ref "E25") (pin "8") (pinfunction "O_8") (pintype "output"))
      (node (ref "E31") (pin "13") (pinfunction "I3_13") (pintype "input"))
    )
    (net (code "93") (name "Net-(E25E-O)") (class "Default")
      (node (ref "E25") (pin "10") (pinfunction "O_10") (pintype "output"))
      (node (ref "E26") (pin "12") (pinfunction "I0_12") (pintype "input"))
      (node (ref "E26") (pin "13") (pinfunction "I1_13") (pintype "input"))
    )
    (net (code "94") (name "Net-(E25F-O)") (class "Default")
      (node (ref "E25") (pin "12") (pinfunction "O_12") (pintype "output"))
      (node (ref "E36") (pin "11") (pinfunction "I0_11") (pintype "input"))
      (node (ref "E36") (pin "12") (pinfunction "I1_12") (pintype "input"))
    )
    (net (code "95") (name "Net-(E30A-Q)") (class "Default")
      (node (ref "E30") (pin "5") (pinfunction "Q_5") (pintype "output"))
      (node (ref "IC10") (pin "7") (pinfunction "I1_7") (pintype "input"))
    )
    (net (code "96") (name "Net-(E30B-CLK)") (class "Default")
      (node (ref "E30") (pin "11") (pinfunction "CLK_11") (pintype "input"))
      (node (ref "IC9") (pin "3") (pinfunction "O_3") (pintype "open_collector"))
      (node (ref "R18") (pin "1") (pinfunction "1_1") (pintype "passive"))
    )
    (net (code "97") (name "Net-(E31A-O)") (class "Default")
      (node (ref "E31") (pin "6") (pinfunction "O_6") (pintype "output"))
      (node (ref "IC9") (pin "1") (pinfunction "I0_1") (pintype "input"))
    )
    (net (code "98") (name "Net-(E31B-O)") (class "Default")
      (node (ref "E31") (pin "8") (pinfunction "O_8") (pintype "output"))
      (node (ref "IC9") (pin "2") (pinfunction "I1_2") (pintype "input"))
    )
    (net (code "99") (name "Net-(E32A-O)") (class "Default")
      (node (ref "E32") (pin "12") (pinfunction "O_12") (pintype "output"))
      (node (ref "E32") (pin "4") (pinfunction "I1_4") (pintype "input"))
      (node (ref "E32") (pin "5") (pinfunction "I2_5") (pintype "input"))
    )
    (net (code "100") (name "Net-(E32C-O)") (class "Default")
      (node (ref "E32") (pin "8") (pinfunction "O_8") (pintype "output"))
      (node (ref "E35") (pin "11") (pinfunction "I0_11") (pintype "input"))
    )
    (net (code "101") (name "Net-(PAD10-P)") (class "Default")
      (node (ref "E38") (pin "1") (pinfunction "1_1") (pintype "passive"))
      (node (ref "PAD10") (pin "1") (pinfunction "P_1") (pintype "passive"))
    )
    (net (code "102") (name "Net-(PAD11-P)") (class "Default")
      (node (ref "E38") (pin "2") (pinfunction "2_2") (pintype "passive"))
      (node (ref "PAD11") (pin "1") (pinfunction "P_1") (pintype "passive"))
    )
    (net (code "103") (name "Net-(PAD12-P)") (class "Default")
      (node (ref "E38") (pin "3") (pinfunction "3_3") (pintype "passive"))
      (node (ref "PAD12") (pin "1") (pinfunction "P_1") (pintype "passive"))
    )
    (net (code "104") (name "Net-(PAD13-P)") (class "Default")
      (node (ref "E38") (pin "4") (pinfunction "4_4") (pintype "passive"))
      (node (ref "PAD13") (pin "1") (pinfunction "P_1") (pintype "passive"))
    )
    (net (code "105") (name "Net-(PAD14-P)") (class "Default")
      (node (ref "E38") (pin "5") (pinfunction "5_5") (pintype "passive"))
      (node (ref "PAD14") (pin "1") (pinfunction "P_1") (pintype "passive"))
    )
    (net (code "106") (name "Net-(PAD15-P)") (class "Default")
      (node (ref "E38") (pin "6") (pinfunction "6_6") (pintype "passive"))
      (node (ref "PAD15") (pin "1") (pinfunction "P_1") (pintype "passive"))
    )
    (net (code "107") (name "Net-(PAD16-P)") (class "Default")
      (node (ref "E38") (pin "7") (pinfunction "7_7") (pintype "passive"))
      (node (ref "PAD16") (pin "1") (pinfunction "P_1") (pintype "passive"))
    )
    (net (code "108") (name "Net-(PAD17-P)") (class "Default")
      (node (ref "E38") (pin "8") (pinfunction "8_8") (pintype "passive"))
      (node (ref "PAD17") (pin "1") (pinfunction "P_1") (pintype "passive"))
    )
    (net (code "109") (name "Net-(PAD18-P)") (class "Default")
      (node (ref "E40") (pin "1") (pinfunction "1_1") (pintype "passive"))
      (node (ref "PAD18") (pin "1") (pinfunction "P_1") (pintype "passive"))
    )
    (net (code "110") (name "Net-(PAD19-P)") (class "Default")
      (node (ref "E40") (pin "2") (pinfunction "2_2") (pintype "passive"))
      (node (ref "PAD19") (pin "1") (pinfunction "P_1") (pintype "passive"))
    )
    (net (code "111") (name "Net-(PAD20-P)") (class "Default")
      (node (ref "E38") (pin "16") (pinfunction "16_16") (pintype "passive"))
      (node (ref "PAD20") (pin "1") (pinfunction "P_1") (pintype "passive"))
    )
    (net (code "112") (name "Net-(PAD21-P)") (class "Default")
      (node (ref "E38") (pin "15") (pinfunction "15_15") (pintype "passive"))
      (node (ref "PAD21") (pin "1") (pinfunction "P_1") (pintype "passive"))
    )
    (net (code "113") (name "Net-(PAD22-P)") (class "Default")
      (node (ref "E38") (pin "14") (pinfunction "14_14") (pintype "passive"))
      (node (ref "PAD22") (pin "1") (pinfunction "P_1") (pintype "passive"))
    )
    (net (code "114") (name "Net-(PAD23-P)") (class "Default")
      (node (ref "E38") (pin "13") (pinfunction "13_13") (pintype "passive"))
      (node (ref "PAD23") (pin "1") (pinfunction "P_1") (pintype "passive"))
    )
    (net (code "115") (name "Net-(PAD24-P)") (class "Default")
      (node (ref "E38") (pin "12") (pinfunction "12_12") (pintype "passive"))
      (node (ref "PAD24") (pin "1") (pinfunction "P_1") (pintype "passive"))
    )
    (net (code "116") (name "Net-(PAD25-P)") (class "Default")
      (node (ref "E38") (pin "11") (pinfunction "11_11") (pintype "passive"))
      (node (ref "PAD25") (pin "1") (pinfunction "P_1") (pintype "passive"))
    )
    (net (code "117") (name "Net-(PAD26-P)") (class "Default")
      (node (ref "E38") (pin "10") (pinfunction "10_10") (pintype "passive"))
      (node (ref "PAD26") (pin "1") (pinfunction "P_1") (pintype "passive"))
    )
    (net (code "118") (name "Net-(PAD27-P)") (class "Default")
      (node (ref "E38") (pin "9") (pinfunction "9_9") (pintype "passive"))
      (node (ref "PAD27") (pin "1") (pinfunction "P_1") (pintype "passive"))
    )
    (net (code "119") (name "Net-(PAD28-P)") (class "Default")
      (node (ref "E40") (pin "3") (pinfunction "3_3") (pintype "passive"))
      (node (ref "PAD28") (pin "1") (pinfunction "P_1") (pintype "passive"))
    )
    (net (code "120") (name "Net-(PAD29-P)") (class "Default")
      (node (ref "E40") (pin "4") (pinfunction "4_4") (pintype "passive"))
      (node (ref "PAD29") (pin "1") (pinfunction "P_1") (pintype "passive"))
    )
    (net (code "121") (name "Net-(PAD30-P)") (class "Default")
      (node (ref "E40") (pin "5") (pinfunction "5_5") (pintype "passive"))
      (node (ref "PAD30") (pin "1") (pinfunction "P_1") (pintype "passive"))
    )
    (net (code "122") (name "Net-(PAD31-P)") (class "Default")
      (node (ref "E40") (pin "6") (pinfunction "6_6") (pintype "passive"))
      (node (ref "PAD31") (pin "1") (pinfunction "P_1") (pintype "passive"))
    )
    (net (code "123") (name "Net-(PAD32-P)") (class "Default")
      (node (ref "E40") (pin "7") (pinfunction "7_7") (pintype "passive"))
      (node (ref "PAD32") (pin "1") (pinfunction "P_1") (pintype "passive"))
    )
    (net (code "124") (name "Net-(PAD33-P)") (class "Default")
      (node (ref "E40") (pin "8") (pinfunction "8_8") (pintype "passive"))
      (node (ref "PAD33") (pin "1") (pinfunction "P_1") (pintype "passive"))
    )
    (net (code "125") (name "Net-(PAD34-P)") (class "Default")
      (node (ref "E40") (pin "16") (pinfunction "16_16") (pintype "passive"))
      (node (ref "PAD34") (pin "1") (pinfunction "P_1") (pintype "passive"))
    )
    (net (code "126") (name "Net-(PAD35-P)") (class "Default")
      (node (ref "E40") (pin "15") (pinfunction "15_15") (pintype "passive"))
      (node (ref "PAD35") (pin "1") (pinfunction "P_1") (pintype "passive"))
    )
    (net (code "127") (name "Net-(PAD36-P)") (class "Default")
      (node (ref "E40") (pin "14") (pinfunction "14_14") (pintype "passive"))
      (node (ref "PAD36") (pin "1") (pinfunction "P_1") (pintype "passive"))
    )
    (net (code "128") (name "Net-(PAD37-P)") (class "Default")
      (node (ref "E40") (pin "13") (pinfunction "13_13") (pintype "passive"))
      (node (ref "PAD37") (pin "1") (pinfunction "P_1") (pintype "passive"))
    )
    (net (code "129") (name "Net-(PAD38-P)") (class "Default")
      (node (ref "E40") (pin "12") (pinfunction "12_12") (pintype "passive"))
      (node (ref "PAD38") (pin "1") (pinfunction "P_1") (pintype "passive"))
    )
    (net (code "130") (name "Net-(PAD39-P)") (class "Default")
      (node (ref "E40") (pin "11") (pinfunction "11_11") (pintype "passive"))
      (node (ref "PAD39") (pin "1") (pinfunction "P_1") (pintype "passive"))
    )
    (net (code "131") (name "Net-(PAD40-P)") (class "Default")
      (node (ref "E40") (pin "10") (pinfunction "10_10") (pintype "passive"))
      (node (ref "PAD40") (pin "1") (pinfunction "P_1") (pintype "passive"))
    )
    (net (code "132") (name "Net-(PAD41-P)") (class "Default")
      (node (ref "E40") (pin "9") (pinfunction "9_9") (pintype "passive"))
      (node (ref "PAD41") (pin "1") (pinfunction "P_1") (pintype "passive"))
    )
    (net (code "133") (name "Net-(PAD42-P)") (class "Default")
      (node (ref "E39") (pin "1") (pinfunction "1_1") (pintype "passive"))
      (node (ref "PAD42") (pin "1") (pinfunction "P_1") (pintype "passive"))
    )
    (net (code "134") (name "Net-(PAD43-P)") (class "Default")
      (node (ref "E39") (pin "2") (pinfunction "2_2") (pintype "passive"))
      (node (ref "PAD43") (pin "1") (pinfunction "P_1") (pintype "passive"))
    )
    (net (code "135") (name "Net-(PAD44-P)") (class "Default")
      (node (ref "E39") (pin "3") (pinfunction "3_3") (pintype "passive"))
      (node (ref "PAD44") (pin "1") (pinfunction "P_1") (pintype "passive"))
    )
    (net (code "136") (name "Net-(PAD45-P)") (class "Default")
      (node (ref "E39") (pin "4") (pinfunction "4_4") (pintype "passive"))
      (node (ref "PAD45") (pin "1") (pinfunction "P_1") (pintype "passive"))
    )
    (net (code "137") (name "Net-(PAD46-P)") (class "Default")
      (node (ref "E39") (pin "5") (pinfunction "5_5") (pintype "passive"))
      (node (ref "PAD46") (pin "1") (pinfunction "P_1") (pintype "passive"))
    )
    (net (code "138") (name "Net-(PAD47-P)") (class "Default")
      (node (ref "E39") (pin "6") (pinfunction "6_6") (pintype "passive"))
      (node (ref "PAD47") (pin "1") (pinfunction "P_1") (pintype "passive"))
    )
    (net (code "139") (name "Net-(PAD48-P)") (class "Default")
      (node (ref "E39") (pin "7") (pinfunction "7_7") (pintype "passive"))
      (node (ref "PAD48") (pin "1") (pinfunction "P_1") (pintype "passive"))
    )
    (net (code "140") (name "Net-(PAD49-P)") (class "Default")
      (node (ref "E39") (pin "8") (pinfunction "8_8") (pintype "passive"))
      (node (ref "PAD49") (pin "1") (pinfunction "P_1") (pintype "passive"))
    )
    (net (code "141") (name "Net-(PAD50-P)") (class "Default")
      (node (ref "E39") (pin "16") (pinfunction "16_16") (pintype "passive"))
      (node (ref "PAD50") (pin "1") (pinfunction "P_1") (pintype "passive"))
    )
    (net (code "142") (name "Net-(PAD51-P)") (class "Default")
      (node (ref "E39") (pin "15") (pinfunction "15_15") (pintype "passive"))
      (node (ref "PAD51") (pin "1") (pinfunction "P_1") (pintype "passive"))
    )
    (net (code "143") (name "Net-(PAD52-P)") (class "Default")
      (node (ref "E39") (pin "14") (pinfunction "14_14") (pintype "passive"))
      (node (ref "PAD52") (pin "1") (pinfunction "P_1") (pintype "passive"))
    )
    (net (code "144") (name "Net-(PAD53-P)") (class "Default")
      (node (ref "E39") (pin "13") (pinfunction "13_13") (pintype "passive"))
      (node (ref "PAD53") (pin "1") (pinfunction "P_1") (pintype "passive"))
    )
    (net (code "145") (name "Net-(PAD54-P)") (class "Default")
      (node (ref "E39") (pin "12") (pinfunction "12_12") (pintype "passive"))
      (node (ref "PAD54") (pin "1") (pinfunction "P_1") (pintype "passive"))
    )
    (net (code "146") (name "Net-(PAD55-P)") (class "Default")
      (node (ref "E39") (pin "11") (pinfunction "11_11") (pintype "passive"))
      (node (ref "PAD55") (pin "1") (pinfunction "P_1") (pintype "passive"))
    )
    (net (code "147") (name "Net-(PAD56-P)") (class "Default")
      (node (ref "E39") (pin "10") (pinfunction "10_10") (pintype "passive"))
      (node (ref "PAD56") (pin "1") (pinfunction "P_1") (pintype "passive"))
    )
    (net (code "148") (name "Net-(PAD57-P)") (class "Default")
      (node (ref "E39") (pin "9") (pinfunction "9_9") (pintype "passive"))
      (node (ref "PAD57") (pin "1") (pinfunction "P_1") (pintype "passive"))
    )
    (net (code "149") (name "PARITY") (class "Default")
      (node (ref "E15") (pin "1") (pinfunction "I0_1") (pintype "input"))
      (node (ref "E15") (pin "13") (pinfunction "I1_13") (pintype "input"))
      (node (ref "E15") (pin "2") (pinfunction "I1_2") (pintype "input"))
      (node (ref "E4") (pin "15") (pinfunction "RCO_15") (pintype "output"))
    )
    (net (code "150") (name "RD") (class "Default")
      (node (ref "E25") (pin "1") (pinfunction "I_1") (pintype "input"))
      (node (ref "E32") (pin "10") (pinfunction "I1_10") (pintype "input"))
      (node (ref "E35") (pin "10") (pinfunction "O_10") (pintype "output"))
    )
    (net (code "151") (name "RUN") (class "Default")
      (node (ref "E18") (pin "11") (pinfunction "I0_11") (pintype "input"))
      (node (ref "E30") (pin "9") (pinfunction "Q_9") (pintype "output"))
      (node (ref "IC9") (pin "6") (pinfunction "I0_6") (pintype "input"))
      (node (ref "IC9") (pin "7") (pinfunction "I1_7") (pintype "input"))
    )
    (net (code "152") (name "RX_DATA") (class "Default")
      (node (ref "E22") (pin "2") (pinfunction "J_2") (pintype "input"))
      (node (ref "E22") (pin "3") (pinfunction "K_3") (pintype "input"))
      (node (ref "E35") (pin "1") (pinfunction "O_1") (pintype "output"))
    )
    (net (code "153") (name "SHIFT") (class "Default")
      (node (ref "E32") (pin "3") (pinfunction "I0_3") (pintype "input"))
      (node (ref "E35") (pin "4") (pinfunction "O_4") (pintype "output"))
    )
    (net (code "154") (name "TR_SKIP") (class "Default")
      (node (ref "E18") (pin "1") (pinfunction "O_1") (pintype "output"))
      (node (ref "E19") (pin "16") (pinfunction "K_16") (pintype "input"))
      (node (ref "E20") (pin "1") (pinfunction "I0_1") (pintype "input"))
      (node (ref "E26") (pin "2") (pinfunction "I1_2") (pintype "input"))
    )
    (net (code "155") (name "VCC") (class "Default")
      (node (ref "C1") (pin "1") (pinfunction "1_1") (pintype "passive"))
      (node (ref "C10") (pin "1") (pinfunction "1_1") (pintype "passive"))
      (node (ref "C11") (pin "1") (pinfunction "1_1") (pintype "passive"))
      (node (ref "C12") (pin "1") (pinfunction "1_1") (pintype "passive"))
      (node (ref "C13") (pin "1") (pinfunction "1_1") (pintype "passive"))
      (node (ref "C14") (pin "1") (pinfunction "1_1") (pintype "passive"))
      (node (ref "C15") (pin "1") (pinfunction "1_1") (pintype "passive"))
      (node (ref "C16") (pin "1") (pinfunction "1_1") (pintype "passive"))
      (node (ref "C17") (pin "1") (pinfunction "1_1") (pintype "passive"))
      (node (ref "C18") (pin "1") (pinfunction "1_1") (pintype "passive"))
      (node (ref "C19") (pin "1") (pinfunction "1_1") (pintype "passive"))
      (node (ref "C2") (pin "1") (pinfunction "1_1") (pintype "passive"))
      (node (ref "C20") (pin "1") (pinfunction "1_1") (pintype "passive"))
      (node (ref "C21") (pin "1") (pinfunction "1_1") (pintype "passive"))
      (node (ref "C22") (pin "1") (pinfunction "1_1") (pintype "passive"))
      (node (ref "C23") (pin "1") (pinfunction "1_1") (pintype "passive"))
      (node (ref "C24") (pin "1") (pinfunction "1_1") (pintype "passive"))
      (node (ref "C25") (pin "1") (pinfunction "1_1") (pintype "passive"))
      (node (ref "C26") (pin "1") (pinfunction "1_1") (pintype "passive"))
      (node (ref "C27") (pin "1") (pinfunction "1_1") (pintype "passive"))
      (node (ref "C28") (pin "1") (pinfunction "1_1") (pintype "passive"))
      (node (ref "C29") (pin "1") (pinfunction "1_1") (pintype "passive"))
      (node (ref "C3") (pin "1") (pinfunction "1_1") (pintype "passive"))
      (node (ref "C30") (pin "1") (pinfunction "1_1") (pintype "passive"))
      (node (ref "C31") (pin "1") (pinfunction "1_1") (pintype "passive"))
      (node (ref "C32") (pin "1") (pinfunction "1_1") (pintype "passive"))
      (node (ref "C33") (pin "1") (pinfunction "1_1") (pintype "passive"))
      (node (ref "C34") (pin "1") (pinfunction "1_1") (pintype "passive"))
      (node (ref "C35") (pin "1") (pinfunction "1_1") (pintype "passive"))
      (node (ref "C36") (pin "1") (pinfunction "1_1") (pintype "passive"))
      (node (ref "C37") (pin "1") (pinfunction "1_1") (pintype "passive"))
      (node (ref "C38") (pin "1") (pinfunction "1_1") (pintype "passive"))
      (node (ref "C39") (pin "1") (pinfunction "1_1") (pintype "passive"))
      (node (ref "C4") (pin "1") (pinfunction "1_1") (pintype "passive"))
      (node (ref "C40") (pin "+") (pinfunction "+_+") (pintype "passive"))
      (node (ref "C5") (pin "1") (pinfunction "1_1") (pintype "passive"))
      (node (ref "C6") (pin "1") (pinfunction "1_1") (pintype "passive"))
      (node (ref "C7") (pin "1") (pinfunction "1_1") (pintype "passive"))
      (node (ref "C8") (pin "1") (pinfunction "1_1") (pintype "passive"))
      (node (ref "C9") (pin "1") (pinfunction "1_1") (pintype "passive"))
      (node (ref "E14") (pin "6") (pinfunction "G1_6") (pintype "input"))
      (node (ref "E16") (pin "10") (pinfunction "PRE_10") (pintype "input"))
      (node (ref "E16") (pin "4") (pinfunction "PRE_4") (pintype "input"))
      (node (ref "E17") (pin "7") (pinfunction "PRE_7") (pintype "input"))
      (node (ref "E2") (pin "1") (pinfunction "CLR_1") (pintype "input"))
      (node (ref "E2") (pin "10") (pinfunction "PRE_10") (pintype "input"))
      (node (ref "E2") (pin "11") (pinfunction "CLK_11") (pintype "input"))
      (node (ref "E2") (pin "12") (pinfunction "D_12") (pintype "input"))
      (node (ref "E2") (pin "13") (pinfunction "CLR_13") (pintype "input"))
      (node (ref "E20") (pin "10") (pinfunction "I1_10") (pintype "input"))
      (node (ref "E20") (pin "9") (pinfunction "I0_9") (pintype "input"))
      (node (ref "E25") (pin "11") (pinfunction "I_11") (pintype "input"))
      (node (ref "E25") (pin "13") (pinfunction "I_13") (pintype "input"))
      (node (ref "E30") (pin "10") (pinfunction "PRE_10") (pintype "input"))
      (node (ref "E30") (pin "12") (pinfunction "D_12") (pintype "input"))
      (node (ref "E30") (pin "4") (pinfunction "PRE_4") (pintype "input"))
      (node (ref "R1") (pin "2") (pinfunction "2_2") (pintype "passive"))
      (node (ref "R18") (pin "2") (pinfunction "2_2") (pintype "passive"))
      (node (ref "R19") (pin "1") (pinfunction "1_1") (pintype "passive"))
      (node (ref "R2") (pin "2") (pinfunction "2_2") (pintype "passive"))
      (node (ref "R20") (pin "2") (pinfunction "2_2") (pintype "passive"))
      (node (ref "R3") (pin "2") (pinfunction "2_2") (pintype "passive"))
      (node (ref "R4") (pin "2") (pinfunction "2_2") (pintype "passive"))
      (node (ref "R5") (pin "2") (pinfunction "2_2") (pintype "passive"))
      (node (ref "R6") (pin "2") (pinfunction "2_2") (pintype "passive"))
      (node (ref "R7") (pin "2") (pinfunction "2_2") (pintype "passive"))
      (node (ref "R8") (pin "2") (pinfunction "2_2") (pintype "passive"))
      (node (ref "R9") (pin "2") (pinfunction "2_2") (pintype "passive"))
      (node (ref "SL1") (pin "1") (pinfunction "S_1") (pintype "passive"))
    )
    (net (code "156") (name "WRT") (class "Default")
      (node (ref "E10") (pin "5") (pinfunction "I2_5") (pintype "input"))
      (node (ref "E15") (pin "10") (pinfunction "I1_10") (pintype "input"))
      (node (ref "E25") (pin "2") (pinfunction "O_2") (pintype "output"))
      (node (ref "IC7") (pin "6") (pinfunction "I0_6") (pintype "input"))
    )
    (net (code "157") (name "XDR2") (class "Default")
      (node (ref "E10") (pin "2") (pinfunction "I1_2") (pintype "input"))
      (node (ref "E5") (pin "12") (pinfunction "I0_12") (pintype "input"))
      (node (ref "E5") (pin "8") (pinfunction "O_8") (pintype "output"))
    )
    (net (code "158") (name "XFER_REQ") (class "Default")
      (node (ref "E19") (pin "4") (pinfunction "J_4") (pintype "input"))
      (node (ref "E20") (pin "12") (pinfunction "I0_12") (pintype "input"))
      (node (ref "E26") (pin "1") (pinfunction "I0_1") (pintype "input"))
      (node (ref "E36") (pin "4") (pinfunction "O_4") (pintype "output"))
    )
    (net (code "159") (name "unconnected-(D34L1-2-PadB)") (class "Default")
      (node (ref "D34L1") (pin "B") (pinfunction "2_B") (pintype "bidirectional"))
    )
    (net (code "160") (name "unconnected-(D34L1-34-PadNN)") (class "Default")
      (node (ref "D34L1") (pin "NN") (pinfunction "34_NN") (pintype "bidirectional"))
    )
    (net (code "161") (name "unconnected-(D34L1-38-PadTT)") (class "Default")
      (node (ref "D34L1") (pin "TT") (pinfunction "38_TT") (pintype "bidirectional"))
    )
    (net (code "162") (name "unconnected-(D34L1-40-PadVV)") (class "Default")
      (node (ref "D34L1") (pin "VV") (pinfunction "40_VV") (pintype "bidirectional"))
    )
    (net (code "163") (name "unconnected-(D34L2-2-PadB)") (class "Default")
      (node (ref "D34L2") (pin "B") (pinfunction "2_B") (pintype "bidirectional"))
    )
    (net (code "164") (name "unconnected-(D34L2-34-PadNN)") (class "Default")
      (node (ref "D34L2") (pin "NN") (pinfunction "34_NN") (pintype "bidirectional"))
    )
    (net (code "165") (name "unconnected-(D34L2-38-PadTT)") (class "Default")
      (node (ref "D34L2") (pin "TT") (pinfunction "38_TT") (pintype "bidirectional"))
    )
    (net (code "166") (name "unconnected-(D34L2-40-PadVV)") (class "Default")
      (node (ref "D34L2") (pin "VV") (pinfunction "40_VV") (pintype "bidirectional"))
    )
    (net (code "167") (name "unconnected-(D35L1-2-PadB)") (class "Default")
      (node (ref "D35L1") (pin "B") (pinfunction "2_B") (pintype "bidirectional"))
    )
    (net (code "168") (name "unconnected-(D35L1-40-PadVV)") (class "Default")
      (node (ref "D35L1") (pin "VV") (pinfunction "40_VV") (pintype "bidirectional"))
    )
    (net (code "169") (name "unconnected-(D35L2-2-PadB)") (class "Default")
      (node (ref "D35L2") (pin "B") (pinfunction "2_B") (pintype "bidirectional"))
    )
    (net (code "170") (name "unconnected-(D35L2-40-PadVV)") (class "Default")
      (node (ref "D35L2") (pin "VV") (pinfunction "40_VV") (pintype "bidirectional"))
    )
    (net (code "171") (name "unconnected-(D36L1-2-PadB)") (class "Default")
      (node (ref "D36L1") (pin "B") (pinfunction "2_B") (pintype "bidirectional"))
    )
    (net (code "172") (name "unconnected-(D36L1-40-PadVV)") (class "Default")
      (node (ref "D36L1") (pin "VV") (pinfunction "40_VV") (pintype "bidirectional"))
    )
    (net (code "173") (name "unconnected-(D36L2-2-PadB)") (class "Default")
      (node (ref "D36L2") (pin "B") (pinfunction "2_B") (pintype "bidirectional"))
    )
    (net (code "174") (name "unconnected-(D36L2-40-PadVV)") (class "Default")
      (node (ref "D36L2") (pin "VV") (pinfunction "40_VV") (pintype "bidirectional"))
    )
    (net (code "175") (name "unconnected-(E2A-Q-Pad5)") (class "Default")
      (node (ref "E2") (pin "5") (pinfunction "Q_5") (pintype "output"))
    )
    (net (code "176") (name "unconnected-(E2B-Q-Pad9)") (class "Default")
      (node (ref "E2") (pin "9") (pinfunction "Q_9") (pintype "output"))
    )
    (net (code "177") (name "unconnected-(E2B-~{Q}-Pad8)") (class "Default")
      (node (ref "E2") (pin "8") (pinfunction "~{Q}_8") (pintype "output"))
    )
    (net (code "178") (name "unconnected-(E4A-QA-Pad14)") (class "Default")
      (node (ref "E4") (pin "14") (pinfunction "QA_14") (pintype "output"))
    )
    (net (code "179") (name "unconnected-(E4A-QB-Pad13)") (class "Default")
      (node (ref "E4") (pin "13") (pinfunction "QB_13") (pintype "output"))
    )
    (net (code "180") (name "unconnected-(E4A-QC-Pad12)") (class "Default")
      (node (ref "E4") (pin "12") (pinfunction "QC_12") (pintype "output"))
    )
    (net (code "181") (name "unconnected-(E4A-QD-Pad11)") (class "Default")
      (node (ref "E4") (pin "11") (pinfunction "QD_11") (pintype "output"))
    )
    (net (code "182") (name "unconnected-(E11A-Y0-Pad15)") (class "Default")
      (node (ref "E11") (pin "15") (pinfunction "Y0_15") (pintype "output"))
    )
    (net (code "183") (name "unconnected-(E11A-Y2-Pad13)") (class "Default")
      (node (ref "E11") (pin "13") (pinfunction "Y2_13") (pintype "output"))
    )
    (net (code "184") (name "unconnected-(E11A-Y3-Pad12)") (class "Default")
      (node (ref "E11") (pin "12") (pinfunction "Y3_12") (pintype "output"))
    )
    (net (code "185") (name "unconnected-(E11A-Y4-Pad11)") (class "Default")
      (node (ref "E11") (pin "11") (pinfunction "Y4_11") (pintype "output"))
    )
    (net (code "186") (name "unconnected-(E11A-Y5-Pad10)") (class "Default")
      (node (ref "E11") (pin "10") (pinfunction "Y5_10") (pintype "output"))
    )
    (net (code "187") (name "unconnected-(E11A-Y6-Pad9)") (class "Default")
      (node (ref "E11") (pin "9") (pinfunction "Y6_9") (pintype "output"))
    )
    (net (code "188") (name "unconnected-(E12A-Y0-Pad15)") (class "Default")
      (node (ref "E12") (pin "15") (pinfunction "Y0_15") (pintype "output"))
    )
    (net (code "189") (name "unconnected-(E12A-Y1-Pad14)") (class "Default")
      (node (ref "E12") (pin "14") (pinfunction "Y1_14") (pintype "output"))
    )
    (net (code "190") (name "unconnected-(E12A-Y4-Pad11)") (class "Default")
      (node (ref "E12") (pin "11") (pinfunction "Y4_11") (pintype "output"))
    )
    (net (code "191") (name "unconnected-(E12A-Y5-Pad10)") (class "Default")
      (node (ref "E12") (pin "10") (pinfunction "Y5_10") (pintype "output"))
    )
    (net (code "192") (name "unconnected-(E12A-Y6-Pad9)") (class "Default")
      (node (ref "E12") (pin "9") (pinfunction "Y6_9") (pintype "output"))
    )
    (net (code "193") (name "unconnected-(E12A-Y7-Pad7)") (class "Default")
      (node (ref "E12") (pin "7") (pinfunction "Y7_7") (pintype "output"))
    )
    (net (code "194") (name "unconnected-(E13A-Y0-Pad15)") (class "Default")
      (node (ref "E13") (pin "15") (pinfunction "Y0_15") (pintype "output"))
    )
    (net (code "195") (name "unconnected-(E13A-Y1-Pad14)") (class "Default")
      (node (ref "E13") (pin "14") (pinfunction "Y1_14") (pintype "output"))
    )
    (net (code "196") (name "unconnected-(E13A-Y2-Pad13)") (class "Default")
      (node (ref "E13") (pin "13") (pinfunction "Y2_13") (pintype "output"))
    )
    (net (code "197") (name "unconnected-(E13A-Y3-Pad12)") (class "Default")
      (node (ref "E13") (pin "12") (pinfunction "Y3_12") (pintype "output"))
    )
    (net (code "198") (name "unconnected-(E17B-Q-Pad11)") (class "Default")
      (node (ref "E17") (pin "11") (pinfunction "Q_11") (pintype "output"))
    )
    (net (code "199") (name "unconnected-(E19A-Q-Pad15)") (class "Default")
      (node (ref "E19") (pin "15") (pinfunction "Q_15") (pintype "output"))
    )
    (net (code "200") (name "unconnected-(E19B-Q-Pad11)") (class "Default")
      (node (ref "E19") (pin "11") (pinfunction "Q_11") (pintype "output"))
    )
    (net (code "201") (name "unconnected-(E20C-O-Pad8)") (class "Default")
      (node (ref "E20") (pin "8") (pinfunction "O_8") (pintype "output"))
    )
    (net (code "202") (name "unconnected-(E21A-~{QD}-Pad11)") (class "Default")
      (node (ref "E21") (pin "11") (pinfunction "~{QD}_11") (pintype "output"))
    )
    (net (code "203") (name "unconnected-(E22A-~{QD}-Pad11)") (class "Default")
      (node (ref "E22") (pin "11") (pinfunction "~{QD}_11") (pintype "output"))
    )
    (net (code "204") (name "unconnected-(E23A-~{QD}-Pad11)") (class "Default")
      (node (ref "E23") (pin "11") (pinfunction "~{QD}_11") (pintype "output"))
    )
    (net (code "205") (name "unconnected-(E26D-O-Pad11)") (class "Default")
      (node (ref "E26") (pin "11") (pinfunction "O_11") (pintype "output"))
    )
    (net (code "206") (name "unconnected-(E30A-~{Q}-Pad6)") (class "Default")
      (node (ref "E30") (pin "6") (pinfunction "~{Q}_6") (pintype "output"))
    )
    (net (code "207") (name "unconnected-(E30B-~{Q}-Pad8)") (class "Default")
      (node (ref "E30") (pin "8") (pinfunction "~{Q}_8") (pintype "output"))
    )
    (net (code "208") (name "unconnected-(E36D-O-Pad13)") (class "Default")
      (node (ref "E36") (pin "13") (pinfunction "O_13") (pintype "output"))
    )
    (net (code "209") (name "unconnected-(LASTDEV-Pad8)") (class "Default")
      (node (ref "LASTDEV") (pin "8") (pinfunction "8_8") (pintype "passive"))
    )
    (net (code "210") (name "unconnected-(LASTDEV-Pad9)") (class "Default")
      (node (ref "LASTDEV") (pin "9") (pinfunction "9_9") (pintype "passive"))
    )
    (net (code "211") (name "unconnected-(LASTDEV-Pad10)") (class "Default")
      (node (ref "LASTDEV") (pin "10") (pinfunction "10_10") (pintype "passive"))
    )
    (net (code "212") (name "~{ACB00}") (class "Default")
      (node (ref "D34L1") (pin "D") (pinfunction "4_D") (pintype "bidirectional"))
      (node (ref "D34L2") (pin "D") (pinfunction "4_D") (pintype "bidirectional"))
      (node (ref "IC6") (pin "3") (pinfunction "O_3") (pintype "open_collector"))
    )
    (net (code "213") (name "~{ACB01}") (class "Default")
      (node (ref "D34L1") (pin "J") (pinfunction "8_J") (pintype "bidirectional"))
      (node (ref "D34L2") (pin "J") (pinfunction "8_J") (pintype "bidirectional"))
      (node (ref "IC6") (pin "5") (pinfunction "O_5") (pintype "open_collector"))
    )
    (net (code "214") (name "~{ACB02}") (class "Default")
      (node (ref "D34L1") (pin "N") (pinfunction "12_N") (pintype "bidirectional"))
      (node (ref "D34L2") (pin "N") (pinfunction "12_N") (pintype "bidirectional"))
      (node (ref "IC1") (pin "3") (pinfunction "O_3") (pintype "open_collector"))
    )
    (net (code "215") (name "~{ACB03}") (class "Default")
      (node (ref "D34L1") (pin "T") (pinfunction "16_T") (pintype "bidirectional"))
      (node (ref "D34L2") (pin "T") (pinfunction "16_T") (pintype "bidirectional"))
      (node (ref "IC2") (pin "5") (pinfunction "O_5") (pintype "open_collector"))
    )
    (net (code "216") (name "~{ACB04}") (class "Default")
      (node (ref "D34L1") (pin "X") (pinfunction "20_X") (pintype "bidirectional"))
      (node (ref "D34L2") (pin "X") (pinfunction "20_X") (pintype "bidirectional"))
      (node (ref "IC1") (pin "5") (pinfunction "O_5") (pintype "open_collector"))
    )
    (net (code "217") (name "~{ACB05}") (class "Default")
      (node (ref "D34L1") (pin "BB") (pinfunction "24_BB") (pintype "bidirectional"))
      (node (ref "D34L2") (pin "BB") (pinfunction "24_BB") (pintype "bidirectional"))
      (node (ref "IC4") (pin "3") (pinfunction "O_3") (pintype "open_collector"))
    )
    (net (code "218") (name "~{ACB06}") (class "Default")
      (node (ref "D34L1") (pin "FF") (pinfunction "28_FF") (pintype "bidirectional"))
      (node (ref "D34L2") (pin "FF") (pinfunction "28_FF") (pintype "bidirectional"))
      (node (ref "IC3") (pin "3") (pinfunction "O_3") (pintype "open_collector"))
    )
    (net (code "219") (name "~{ACB07}") (class "Default")
      (node (ref "D34L1") (pin "LL") (pinfunction "32_LL") (pintype "bidirectional"))
      (node (ref "D34L2") (pin "LL") (pinfunction "32_LL") (pintype "bidirectional"))
      (node (ref "IC3") (pin "5") (pinfunction "O_5") (pintype "open_collector"))
    )
    (net (code "220") (name "~{ACB08}") (class "Default")
      (node (ref "D34L1") (pin "RR") (pinfunction "36_RR") (pintype "bidirectional"))
      (node (ref "D34L2") (pin "RR") (pinfunction "36_RR") (pintype "bidirectional"))
      (node (ref "IC4") (pin "5") (pinfunction "O_5") (pintype "open_collector"))
    )
    (net (code "221") (name "~{ACB09}") (class "Default")
      (node (ref "D34L1") (pin "F") (pinfunction "6_F") (pintype "bidirectional"))
      (node (ref "D34L2") (pin "F") (pinfunction "6_F") (pintype "bidirectional"))
      (node (ref "IC5") (pin "3") (pinfunction "O_3") (pintype "open_collector"))
    )
    (net (code "222") (name "~{ACB10}") (class "Default")
      (node (ref "D34L1") (pin "L") (pinfunction "10_L") (pintype "bidirectional"))
      (node (ref "D34L2") (pin "L") (pinfunction "10_L") (pintype "bidirectional"))
      (node (ref "IC5") (pin "5") (pinfunction "O_5") (pintype "open_collector"))
    )
    (net (code "223") (name "~{ACB11}") (class "Default")
      (node (ref "D34L1") (pin "R") (pinfunction "14_R") (pintype "bidirectional"))
      (node (ref "D34L2") (pin "R") (pinfunction "14_R") (pintype "bidirectional"))
      (node (ref "IC2") (pin "3") (pinfunction "O_3") (pintype "open_collector"))
    )
    (net (code "224") (name "~{ACCLEAR}") (class "Default")
      (node (ref "D34L1") (pin "DD") (pinfunction "26_DD") (pintype "bidirectional"))
      (node (ref "D34L2") (pin "DD") (pinfunction "26_DD") (pintype "bidirectional"))
      (node (ref "IC7") (pin "3") (pinfunction "O_3") (pintype "open_collector"))
    )
    (net (code "225") (name "~{BMB03}") (class "Default")
      (node (ref "D35L1") (pin "T") (pinfunction "16_T") (pintype "bidirectional"))
      (node (ref "D35L2") (pin "T") (pinfunction "16_T") (pintype "bidirectional"))
    )
    (net (code "226") (name "~{BMB04}") (class "Default")
      (node (ref "D35L1") (pin "BB") (pinfunction "24_BB") (pintype "bidirectional"))
      (node (ref "D35L2") (pin "BB") (pinfunction "24_BB") (pintype "bidirectional"))
    )
    (net (code "227") (name "~{BMB05}") (class "Default")
      (node (ref "D35L1") (pin "LL") (pinfunction "32_LL") (pintype "bidirectional"))
      (node (ref "D35L2") (pin "LL") (pinfunction "32_LL") (pintype "bidirectional"))
    )
    (net (code "228") (name "~{BMB06}") (class "Default")
      (node (ref "D35L1") (pin "F") (pinfunction "6_F") (pintype "bidirectional"))
      (node (ref "D35L2") (pin "F") (pinfunction "6_F") (pintype "bidirectional"))
    )
    (net (code "229") (name "~{BMB07}") (class "Default")
      (node (ref "D35L1") (pin "R") (pinfunction "14_R") (pintype "bidirectional"))
      (node (ref "D35L2") (pin "R") (pinfunction "14_R") (pintype "bidirectional"))
    )
    (net (code "230") (name "~{BMB08}") (class "Default")
      (node (ref "D35L1") (pin "Z") (pinfunction "22_Z") (pintype "bidirectional"))
      (node (ref "D35L2") (pin "Z") (pinfunction "22_Z") (pintype "bidirectional"))
    )
    (net (code "231") (name "~{BRUN}") (class "Default")
      (node (ref "D34L1") (pin "JJ") (pinfunction "30_JJ") (pintype "bidirectional"))
      (node (ref "D34L2") (pin "JJ") (pinfunction "30_JJ") (pintype "bidirectional"))
    )
    (net (code "232") (name "~{CLK_PARITY}") (class "Default")
      (node (ref "E17") (pin "6") (pinfunction "CLK_6") (pintype "input"))
      (node (ref "E32") (pin "6") (pinfunction "O_6") (pintype "output"))
      (node (ref "E5") (pin "4") (pinfunction "I0_4") (pintype "input"))
      (node (ref "E5") (pin "5") (pinfunction "I1_5") (pintype "input"))
    )
    (net (code "233") (name "~{DONE}") (class "Default")
      (node (ref "E10") (pin "4") (pinfunction "I1_4") (pintype "input"))
      (node (ref "E25") (pin "4") (pinfunction "O_4") (pintype "output"))
      (node (ref "E31") (pin "12") (pinfunction "I2_12") (pintype "input"))
    )
    (net (code "234") (name "~{ENB_BUF_LD}") (class "Default")
      (node (ref "E21") (pin "9") (pinfunction "S/~{L}_9") (pintype "input"))
      (node (ref "E22") (pin "9") (pinfunction "S/~{L}_9") (pintype "input"))
      (node (ref "E23") (pin "9") (pinfunction "S/~{L}_9") (pintype "input"))
      (node (ref "E24") (pin "11") (pinfunction "O_11") (pintype "output"))
      (node (ref "E32") (pin "13") (pinfunction "I2_13") (pintype "input"))
      (node (ref "E32") (pin "2") (pinfunction "I1_2") (pintype "input"))
      (node (ref "E4") (pin "9") (pinfunction "LD_9") (pintype "input"))
    )
    (net (code "235") (name "~{INIT1}") (class "Default")
      (node (ref "E11") (pin "7") (pinfunction "Y7_7") (pintype "output"))
      (node (ref "E2") (pin "4") (pinfunction "PRE_4") (pintype "input"))
    )
    (net (code "236") (name "~{INIT4}") (class "Default")
      (node (ref "E13") (pin "7") (pinfunction "Y7_7") (pintype "output"))
      (node (ref "E2") (pin "3") (pinfunction "CLK_3") (pintype "input"))
    )
    (net (code "237") (name "~{INIT}") (class "Default")
      (node (ref "E15") (pin "6") (pinfunction "O_6") (pintype "output"))
      (node (ref "E16") (pin "1") (pinfunction "CLR_1") (pintype "input"))
      (node (ref "E16") (pin "13") (pinfunction "CLR_13") (pintype "input"))
      (node (ref "E17") (pin "3") (pinfunction "CLR_3") (pintype "input"))
      (node (ref "E19") (pin "3") (pinfunction "CLR_3") (pintype "input"))
      (node (ref "E19") (pin "8") (pinfunction "CLR_8") (pintype "input"))
      (node (ref "E21") (pin "1") (pinfunction "CLR_1") (pintype "input"))
      (node (ref "E22") (pin "1") (pinfunction "CLR_1") (pintype "input"))
      (node (ref "E23") (pin "1") (pinfunction "CLR_1") (pintype "input"))
      (node (ref "E24") (pin "9") (pinfunction "I0_9") (pintype "input"))
      (node (ref "E30") (pin "1") (pinfunction "CLR_1") (pintype "input"))
      (node (ref "E4") (pin "1") (pinfunction "CLR_1") (pintype "input"))
    )
    (net (code "238") (name "~{INTR4}") (class "Default")
      (node (ref "E13") (pin "9") (pinfunction "Y6_9") (pintype "output"))
      (node (ref "E30") (pin "3") (pinfunction "CLK_3") (pintype "input"))
    )
    (net (code "239") (name "~{INT_RQ}") (class "Default")
      (node (ref "D34L1") (pin "Z") (pinfunction "22_Z") (pintype "bidirectional"))
      (node (ref "D34L2") (pin "Z") (pinfunction "22_Z") (pintype "bidirectional"))
      (node (ref "IC10") (pin "5") (pinfunction "O_5") (pintype "open_collector"))
    )
    (net (code "240") (name "~{IOS}") (class "Default")
      (node (ref "D34L1") (pin "V") (pinfunction "18_V") (pintype "bidirectional"))
      (node (ref "D34L2") (pin "V") (pinfunction "18_V") (pintype "bidirectional"))
      (node (ref "IC10") (pin "3") (pinfunction "O_3") (pintype "open_collector"))
    )
    (net (code "241") (name "~{LCD1}") (class "Default")
      (node (ref "E10") (pin "9") (pinfunction "I0_9") (pintype "input"))
      (node (ref "E11") (pin "14") (pinfunction "Y1_14") (pintype "output"))
      (node (ref "E16") (pin "11") (pinfunction "CLK_11") (pintype "input"))
      (node (ref "E16") (pin "3") (pinfunction "CLK_3") (pintype "input"))
      (node (ref "E24") (pin "5") (pinfunction "I1_5") (pintype "input"))
      (node (ref "E25") (pin "5") (pinfunction "I_5") (pintype "input"))
    )
    (net (code "242") (name "~{MAINT}") (class "Default")
      (node (ref "E10") (pin "3") (pinfunction "I0_3") (pintype "input"))
      (node (ref "E16") (pin "8") (pinfunction "~{Q}_8") (pintype "output"))
      (node (ref "E17") (pin "2") (pinfunction "PRE_2") (pintype "input"))
      (node (ref "E19") (pin "2") (pinfunction "PRE_2") (pintype "input"))
      (node (ref "E19") (pin "7") (pinfunction "PRE_7") (pintype "input"))
      (node (ref "E24") (pin "13") (pinfunction "I1_13") (pintype "input"))
      (node (ref "E31") (pin "5") (pinfunction "I3_5") (pintype "input"))
      (node (ref "E31") (pin "9") (pinfunction "I0_9") (pintype "input"))
    )
    (net (code "243") (name "~{MYDEV}") (class "Default")
      (node (ref "E11") (pin "4") (pinfunction "G2A_4") (pintype "input"))
      (node (ref "E12") (pin "4") (pinfunction "G2A_4") (pintype "input"))
      (node (ref "E13") (pin "4") (pinfunction "G2A_4") (pintype "input"))
      (node (ref "IOT") (pin "1") (pinfunction "P_1") (pintype "passive"))
    )
    (net (code "244") (name "~{PARITY}") (class "Default")
      (node (ref "E15") (pin "12") (pinfunction "I0_12") (pintype "input"))
      (node (ref "E17") (pin "10") (pinfunction "~{Q}_10") (pintype "output"))
    )
    (net (code "245") (name "~{RX_12_BIT}") (class "Default")
      (node (ref "DRIVE") (pin "FF") (pinfunction "28_FF") (pintype "bidirectional"))
      (node (ref "IC8") (pin "3") (pinfunction "O_3") (pintype "open_collector"))
      (node (ref "R16") (pin "2") (pinfunction "2_2") (pintype "passive"))
      (node (ref "R7") (pin "1") (pinfunction "1_1") (pintype "passive"))
    )
    (net (code "246") (name "~{RX_DATA}") (class "Default")
      (node (ref "DRIVE") (pin "BB") (pinfunction "24_BB") (pintype "bidirectional"))
      (node (ref "E35") (pin "2") (pinfunction "I0_2") (pintype "input"))
      (node (ref "IC7") (pin "5") (pinfunction "O_5") (pintype "open_collector"))
      (node (ref "R17") (pin "2") (pinfunction "2_2") (pintype "passive"))
      (node (ref "R8") (pin "1") (pinfunction "1_1") (pintype "passive"))
    )
    (net (code "247") (name "~{RX_DONE}") (class "Default")
      (node (ref "DRIVE") (pin "X") (pinfunction "20_X") (pintype "bidirectional"))
      (node (ref "E36") (pin "8") (pinfunction "I0_8") (pintype "input"))
      (node (ref "R13") (pin "2") (pinfunction "2_2") (pintype "passive"))
      (node (ref "R4") (pin "1") (pinfunction "1_1") (pintype "passive"))
    )
    (net (code "248") (name "~{RX_ERROR}") (class "Default")
      (node (ref "DRIVE") (pin "J") (pinfunction "8_J") (pintype "bidirectional"))
      (node (ref "E36") (pin "3") (pinfunction "I1_3") (pintype "input"))
      (node (ref "R14") (pin "2") (pinfunction "2_2") (pintype "passive"))
      (node (ref "R5") (pin "1") (pinfunction "1_1") (pintype "passive"))
    )
    (net (code "249") (name "~{RX_INIT}") (class "Default")
      (node (ref "DRIVE") (pin "N") (pinfunction "12_N") (pintype "bidirectional"))
      (node (ref "IC8") (pin "5") (pinfunction "O_5") (pintype "open_collector"))
      (node (ref "R20") (pin "1") (pinfunction "1_1") (pintype "passive"))
      (node (ref "R9") (pin "1") (pinfunction "1_1") (pintype "passive"))
    )
    (net (code "250") (name "~{RX_OUT}") (class "Default")
      (node (ref "DRIVE") (pin "RR") (pinfunction "36_RR") (pintype "bidirectional"))
      (node (ref "E35") (pin "8") (pinfunction "I0_8") (pintype "input"))
      (node (ref "R12") (pin "2") (pinfunction "2_2") (pintype "passive"))
      (node (ref "R3") (pin "1") (pinfunction "1_1") (pintype "passive"))
    )
    (net (code "251") (name "~{RX_RUN}") (class "Default")
      (node (ref "DRIVE") (pin "D") (pinfunction "4_D") (pintype "bidirectional"))
      (node (ref "IC9") (pin "5") (pinfunction "O_5") (pintype "open_collector"))
      (node (ref "R15") (pin "2") (pinfunction "2_2") (pintype "passive"))
      (node (ref "R6") (pin "1") (pinfunction "1_1") (pintype "passive"))
    )
    (net (code "252") (name "~{RX_SHIFT}") (class "Default")
      (node (ref "DRIVE") (pin "LL") (pinfunction "32_LL") (pintype "bidirectional"))
      (node (ref "E35") (pin "5") (pinfunction "I0_5") (pintype "input"))
      (node (ref "R10") (pin "2") (pinfunction "2_2") (pintype "passive"))
      (node (ref "R2") (pin "1") (pinfunction "1_1") (pintype "passive"))
    )
    (net (code "253") (name "~{RX_TR_REQ}") (class "Default")
      (node (ref "DRIVE") (pin "T") (pinfunction "16_T") (pintype "bidirectional"))
      (node (ref "E36") (pin "5") (pinfunction "I0_5") (pintype "input"))
      (node (ref "R1") (pin "1") (pinfunction "1_1") (pintype "passive"))
      (node (ref "R11") (pin "2") (pinfunction "2_2") (pintype "passive"))
    )
    (net (code "254") (name "~{SDN4}") (class "Default")
      (node (ref "E13") (pin "10") (pinfunction "Y5_10") (pintype "output"))
      (node (ref "E18") (pin "8") (pinfunction "I0_8") (pintype "input"))
    )
    (net (code "255") (name "~{SER4}") (class "Default")
      (node (ref "E13") (pin "11") (pinfunction "Y4_11") (pintype "output"))
      (node (ref "E18") (pin "5") (pinfunction "I0_5") (pintype "input"))
    )
    (net (code "256") (name "~{STR2}") (class "Default")
      (node (ref "E12") (pin "12") (pinfunction "Y3_12") (pintype "output"))
      (node (ref "E18") (pin "2") (pinfunction "I0_2") (pintype "input"))
    )
    (net (code "257") (name "~{XDR2}") (class "Default")
      (node (ref "E12") (pin "13") (pinfunction "Y2_13") (pintype "output"))
      (node (ref "E24") (pin "4") (pinfunction "I0_4") (pintype "input"))
      (node (ref "E25") (pin "9") (pinfunction "I_9") (pintype "input"))
      (node (ref "E35") (pin "12") (pinfunction "I1_12") (pintype "input"))
      (node (ref "E5") (pin "10") (pinfunction "I1_10") (pintype "input"))
      (node (ref "E5") (pin "9") (pinfunction "I0_9") (pintype "input"))
    )
  )
)
